# INC-IO1616001.net
KiCad netlist of a schematic drawn in Altium Designer
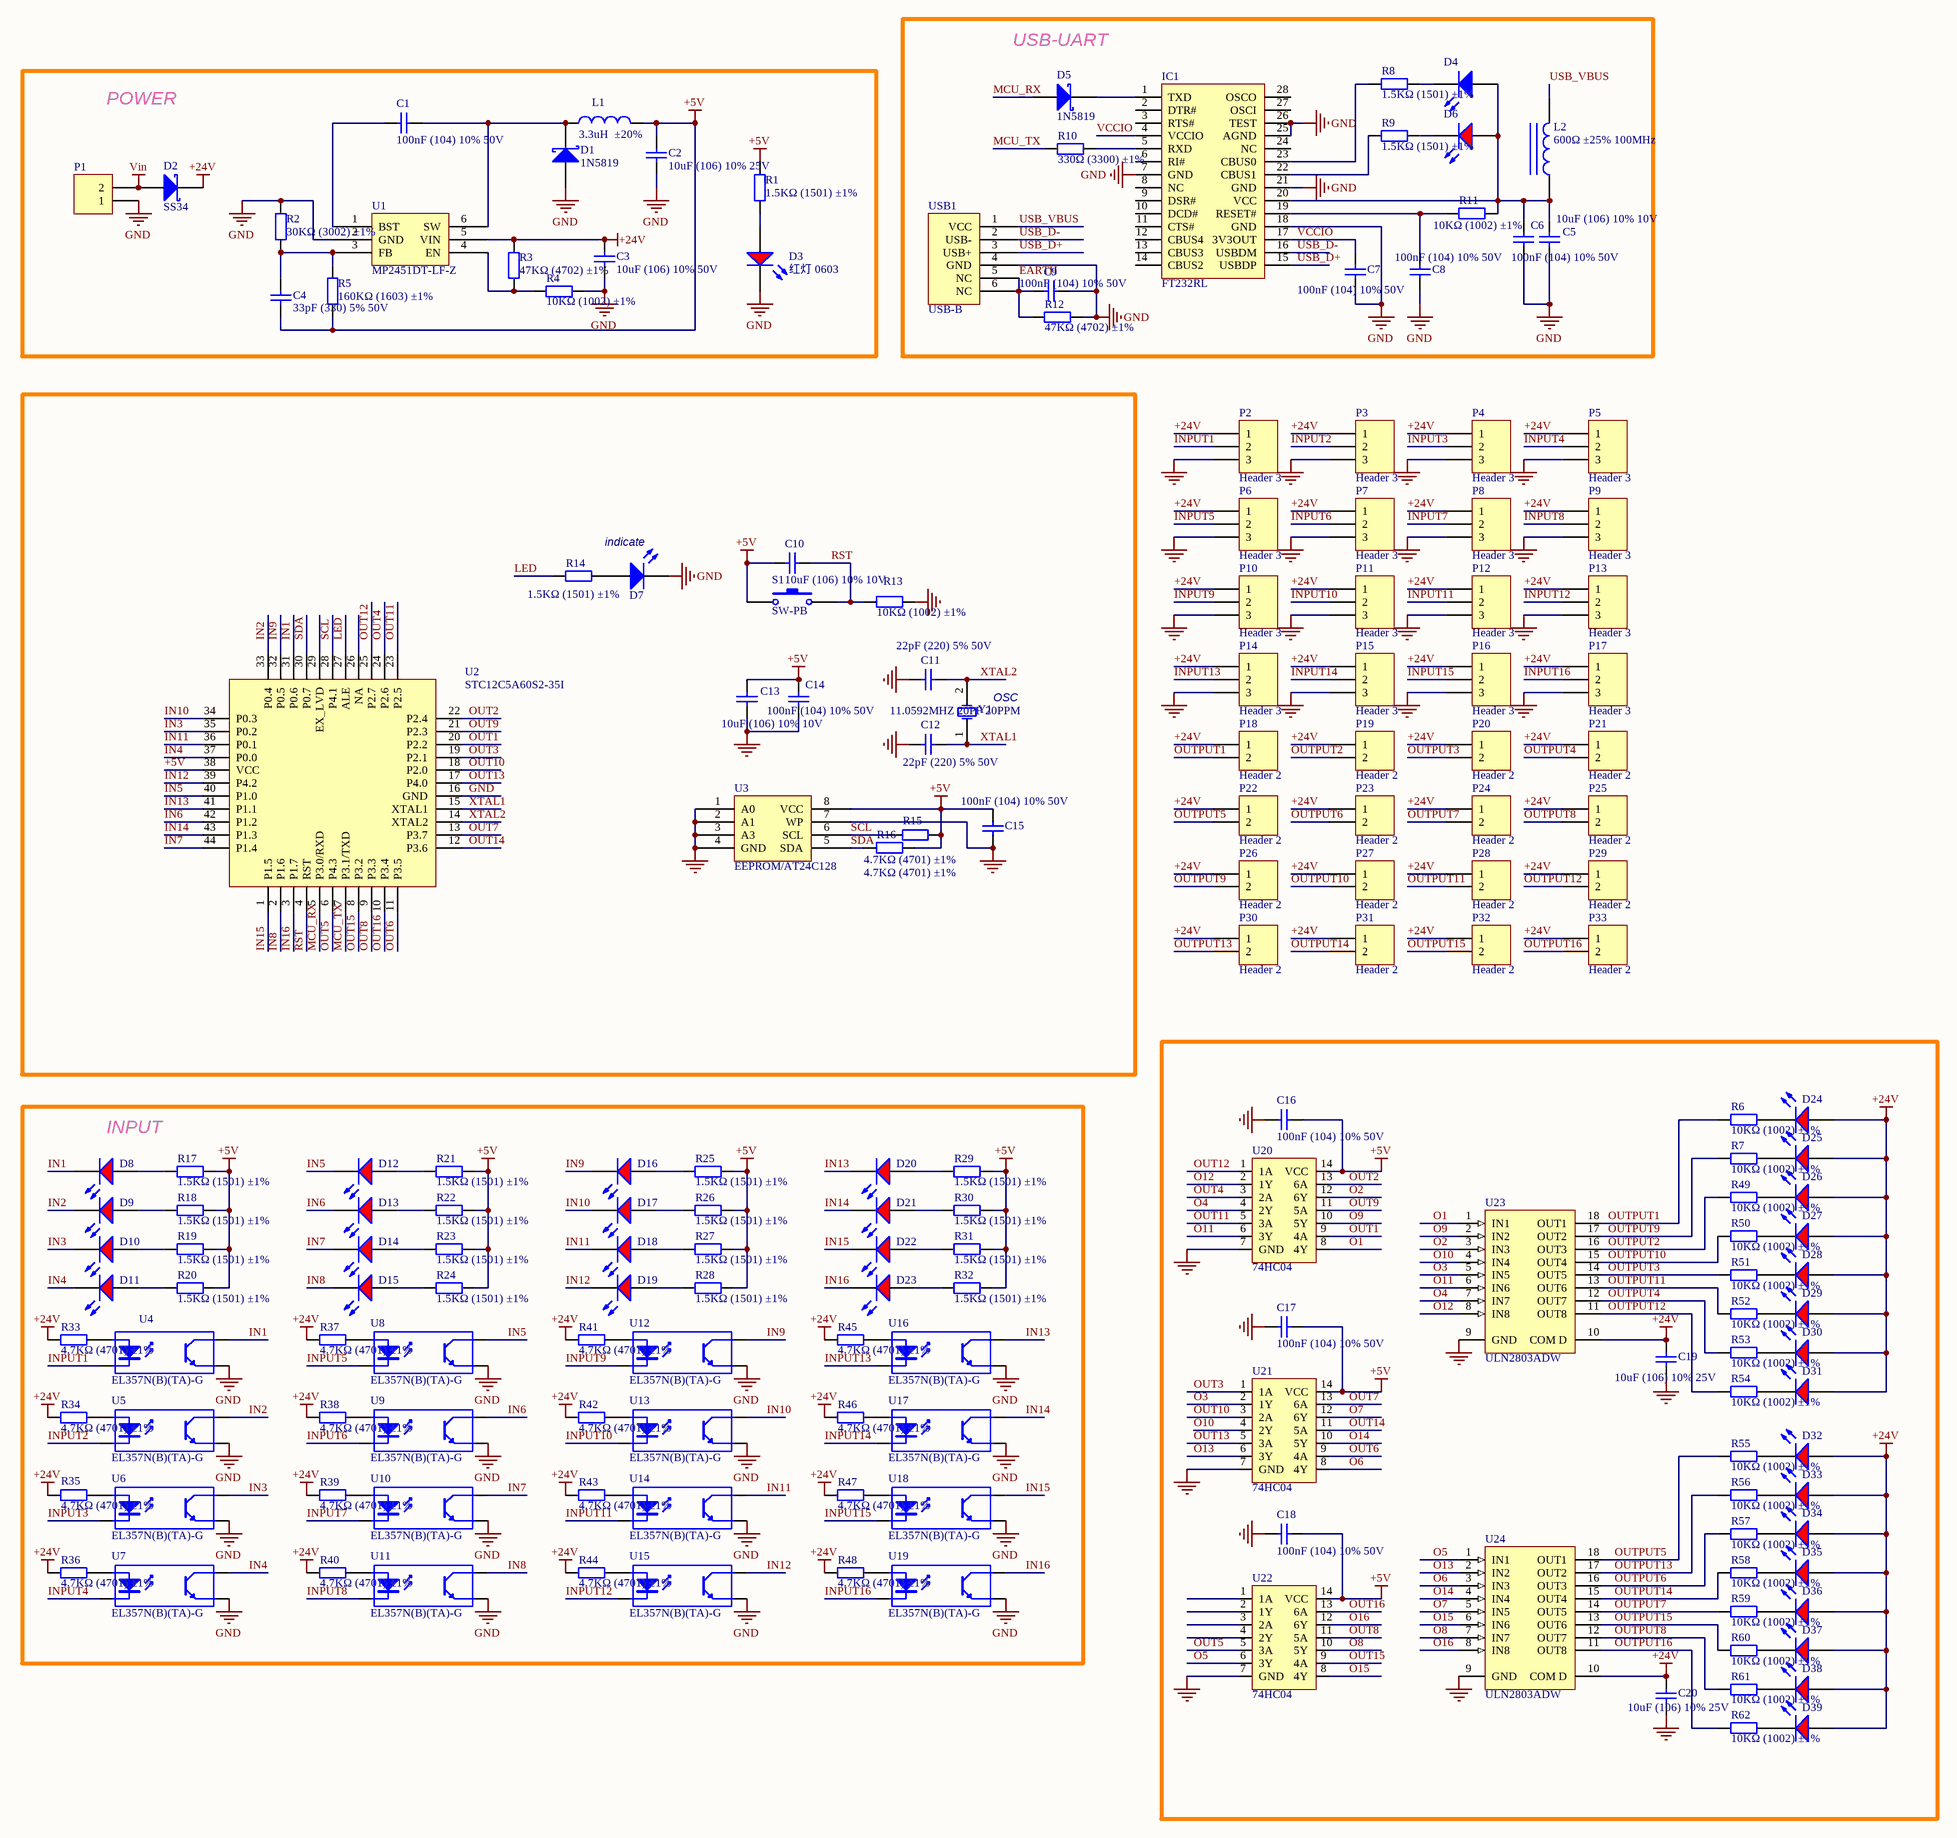
[diagram p0: INC-IO1616001.SchDoc]

(export (version "E")
  (design (tool "Eeschema 10.0.6"))
  (components
    (comp (ref "C1")
      (value "100nF (104) 10% 50V")
      (footprint "0603_C")
      (description "贴片电容")
      (libsource (lib "Miscellaneous Devices LC") (part "0603 100nF (104) 10% 50V"))
    )
    (comp (ref "C2")
      (value "10uF (106) 10% 25V")
      (footprint "0805_C")
      (description "贴片电容")
      (libsource (lib "Miscellaneous Devices LC") (part "0805 10uF (106) 10% 25V"))
    )
    (comp (ref "C3")
      (value "10uF (106) 10% 50V")
      (footprint "1206_C")
      (description "贴片电容")
      (libsource (lib "Miscellaneous Devices LC") (part "1206 10uF (106) 10% 50V"))
    )
    (comp (ref "C4")
      (value "33pF (330) 5% 50V")
      (footprint "0603_C")
      (description "贴片电容")
      (libsource (lib "Miscellaneous Devices LC") (part "0603 33pF (330) 5% 50V"))
    )
    (comp (ref "C5")
      (value "10uF (106) 10% 10V")
      (footprint "0603_C")
      (description "贴片电容")
      (libsource (lib "Miscellaneous Devices LC") (part "0603 10uF (106) 10% 10V"))
    )
    (comp (ref "C6")
      (value "100nF (104) 10% 50V")
      (footprint "0603_C")
      (description "贴片电容")
      (libsource (lib "Miscellaneous Devices LC") (part "0603 100nF (104) 10% 50V"))
    )
    (comp (ref "C7")
      (value "100nF (104) 10% 50V")
      (footprint "0603_C")
      (description "贴片电容")
      (libsource (lib "Miscellaneous Devices LC") (part "0603 100nF (104) 10% 50V"))
    )
    (comp (ref "C8")
      (value "100nF (104) 10% 50V")
      (footprint "0603_C")
      (description "贴片电容")
      (libsource (lib "Miscellaneous Devices LC") (part "0603 100nF (104) 10% 50V"))
    )
    (comp (ref "C9")
      (value "100nF (104) 10% 50V")
      (footprint "0603_C")
      (description "贴片电容")
      (libsource (lib "Miscellaneous Devices LC") (part "0603 100nF (104) 10% 50V"))
    )
    (comp (ref "C10")
      (value "10uF (106) 10% 10V")
      (footprint "0603_C")
      (description "贴片电容")
      (libsource (lib "Miscellaneous Devices LC") (part "0603 10uF (106) 10% 10V"))
    )
    (comp (ref "C11")
      (value "22pF (220) 5% 50V")
      (footprint "0603_C")
      (description "贴片电容")
      (libsource (lib "Miscellaneous Devices LC") (part "0603 22pF (220) 5% 50V"))
    )
    (comp (ref "C12")
      (value "22pF (220) 5% 50V")
      (footprint "0603_C")
      (description "贴片电容")
      (libsource (lib "Miscellaneous Devices LC") (part "0603 22pF (220) 5% 50V"))
    )
    (comp (ref "C13")
      (value "10uF (106) 10% 10V")
      (footprint "0603_C")
      (description "贴片电容")
      (libsource (lib "Miscellaneous Devices LC") (part "0603 10uF (106) 10% 10V"))
    )
    (comp (ref "C14")
      (value "100nF (104) 10% 50V")
      (footprint "0603_C")
      (description "贴片电容")
      (libsource (lib "Miscellaneous Devices LC") (part "0603 100nF (104) 10% 50V"))
    )
    (comp (ref "C15")
      (value "100nF (104) 10% 50V")
      (footprint "0603_C")
      (description "贴片电容")
      (libsource (lib "Miscellaneous Devices LC") (part "0603 100nF (104) 10% 50V"))
    )
    (comp (ref "C16")
      (value "100nF (104) 10% 50V")
      (footprint "0603_C")
      (description "贴片电容")
      (libsource (lib "Miscellaneous Devices LC") (part "0603 100nF (104) 10% 50V"))
    )
    (comp (ref "C17")
      (value "100nF (104) 10% 50V")
      (footprint "0603_C")
      (description "贴片电容")
      (libsource (lib "Miscellaneous Devices LC") (part "0603 100nF (104) 10% 50V"))
    )
    (comp (ref "C18")
      (value "100nF (104) 10% 50V")
      (footprint "0603_C")
      (description "贴片电容")
      (libsource (lib "Miscellaneous Devices LC") (part "0603 100nF (104) 10% 50V"))
    )
    (comp (ref "C19")
      (value "10uF (106) 10% 25V")
      (footprint "0805_C")
      (description "贴片电容")
      (libsource (lib "Miscellaneous Devices LC") (part "0805 10uF (106) 10% 25V"))
    )
    (comp (ref "C20")
      (value "10uF (106) 10% 25V")
      (footprint "0805_C")
      (description "贴片电容")
      (libsource (lib "Miscellaneous Devices LC") (part "0805 10uF (106) 10% 25V"))
    )
    (comp (ref "D1")
      (value "1N5819")
      (footprint "SOD-123")
      (description "Schottky Diode")
      (fields (field (name "PUBLISHER") "Altium Limited"))
      (libsource (lib "Miscellaneous Devices") (part "D Schottky"))
    )
    (comp (ref "D2")
      (value "SS34")
      (footprint "SMA(DO-214AC)_S1")
      (description "Schottky Diode")
      (fields (field (name "PUBLISHER") "Altium Limited"))
      (libsource (lib "Miscellaneous Devices") (part "D Schottky"))
    )
    (comp (ref "D3")
      (value "红灯 0603")
      (footprint "0603_LED_S1")
      (description "发光二极管")
      (libsource (lib "Miscellaneous Devices LC") (part "0603 红灯"))
    )
    (comp (ref "D4")
      (value "蓝灯 0603")
      (footprint "0603_LED_S1")
      (description "发光二极管")
      (libsource (lib "Miscellaneous Devices LC") (part "0603 蓝灯"))
    )
    (comp (ref "D5")
      (value "1N5819")
      (footprint "SOD-123")
      (description "Schottky Diode")
      (fields (field (name "PUBLISHER") "Altium Limited"))
      (libsource (lib "Miscellaneous Devices") (part "D Schottky"))
    )
    (comp (ref "D6")
      (value "红灯 0603")
      (footprint "0603_LED_S1")
      (description "发光二极管")
      (libsource (lib "Miscellaneous Devices LC") (part "0603 红灯"))
    )
    (comp (ref "D7")
      (value "蓝灯 0603")
      (footprint "0603_LED_S1")
      (description "发光二极管")
      (libsource (lib "Miscellaneous Devices LC") (part "0603 蓝灯"))
    )
    (comp (ref "D8")
      (value "红灯 0603")
      (footprint "0603_LED_S1")
      (description "发光二极管")
      (libsource (lib "Miscellaneous Devices LC") (part "0603 红灯"))
    )
    (comp (ref "D9")
      (value "红灯 0603")
      (footprint "0603_LED_S1")
      (description "发光二极管")
      (libsource (lib "Miscellaneous Devices LC") (part "0603 红灯"))
    )
    (comp (ref "D10")
      (value "红灯 0603")
      (footprint "0603_LED_S1")
      (description "发光二极管")
      (libsource (lib "Miscellaneous Devices LC") (part "0603 红灯"))
    )
    (comp (ref "D11")
      (value "红灯 0603")
      (footprint "0603_LED_S1")
      (description "发光二极管")
      (libsource (lib "Miscellaneous Devices LC") (part "0603 红灯"))
    )
    (comp (ref "D12")
      (value "红灯 0603")
      (footprint "0603_LED_S1")
      (description "发光二极管")
      (libsource (lib "Miscellaneous Devices LC") (part "0603 红灯"))
    )
    (comp (ref "D13")
      (value "红灯 0603")
      (footprint "0603_LED_S1")
      (description "发光二极管")
      (libsource (lib "Miscellaneous Devices LC") (part "0603 红灯"))
    )
    (comp (ref "D14")
      (value "红灯 0603")
      (footprint "0603_LED_S1")
      (description "发光二极管")
      (libsource (lib "Miscellaneous Devices LC") (part "0603 红灯"))
    )
    (comp (ref "D15")
      (value "红灯 0603")
      (footprint "0603_LED_S1")
      (description "发光二极管")
      (libsource (lib "Miscellaneous Devices LC") (part "0603 红灯"))
    )
    (comp (ref "D16")
      (value "红灯 0603")
      (footprint "0603_LED_S1")
      (description "发光二极管")
      (libsource (lib "Miscellaneous Devices LC") (part "0603 红灯"))
    )
    (comp (ref "D17")
      (value "红灯 0603")
      (footprint "0603_LED_S1")
      (description "发光二极管")
      (libsource (lib "Miscellaneous Devices LC") (part "0603 红灯"))
    )
    (comp (ref "D18")
      (value "红灯 0603")
      (footprint "0603_LED_S1")
      (description "发光二极管")
      (libsource (lib "Miscellaneous Devices LC") (part "0603 红灯"))
    )
    (comp (ref "D19")
      (value "红灯 0603")
      (footprint "0603_LED_S1")
      (description "发光二极管")
      (libsource (lib "Miscellaneous Devices LC") (part "0603 红灯"))
    )
    (comp (ref "D20")
      (value "红灯 0603")
      (footprint "0603_LED_S1")
      (description "发光二极管")
      (libsource (lib "Miscellaneous Devices LC") (part "0603 红灯"))
    )
    (comp (ref "D21")
      (value "红灯 0603")
      (footprint "0603_LED_S1")
      (description "发光二极管")
      (libsource (lib "Miscellaneous Devices LC") (part "0603 红灯"))
    )
    (comp (ref "D22")
      (value "红灯 0603")
      (footprint "0603_LED_S1")
      (description "发光二极管")
      (libsource (lib "Miscellaneous Devices LC") (part "0603 红灯"))
    )
    (comp (ref "D23")
      (value "红灯 0603")
      (footprint "0603_LED_S1")
      (description "发光二极管")
      (libsource (lib "Miscellaneous Devices LC") (part "0603 红灯"))
    )
    (comp (ref "D24")
      (value "红灯 0603")
      (footprint "0603_LED_S1")
      (description "发光二极管")
      (libsource (lib "Miscellaneous Devices LC") (part "0603 红灯"))
    )
    (comp (ref "D25")
      (value "红灯 0603")
      (footprint "0603_LED_S1")
      (description "发光二极管")
      (libsource (lib "Miscellaneous Devices LC") (part "0603 红灯"))
    )
    (comp (ref "D26")
      (value "红灯 0603")
      (footprint "0603_LED_S1")
      (description "发光二极管")
      (libsource (lib "Miscellaneous Devices LC") (part "0603 红灯"))
    )
    (comp (ref "D27")
      (value "红灯 0603")
      (footprint "0603_LED_S1")
      (description "发光二极管")
      (libsource (lib "Miscellaneous Devices LC") (part "0603 红灯"))
    )
    (comp (ref "D28")
      (value "红灯 0603")
      (footprint "0603_LED_S1")
      (description "发光二极管")
      (libsource (lib "Miscellaneous Devices LC") (part "0603 红灯"))
    )
    (comp (ref "D29")
      (value "红灯 0603")
      (footprint "0603_LED_S1")
      (description "发光二极管")
      (libsource (lib "Miscellaneous Devices LC") (part "0603 红灯"))
    )
    (comp (ref "D30")
      (value "红灯 0603")
      (footprint "0603_LED_S1")
      (description "发光二极管")
      (libsource (lib "Miscellaneous Devices LC") (part "0603 红灯"))
    )
    (comp (ref "D31")
      (value "红灯 0603")
      (footprint "0603_LED_S1")
      (description "发光二极管")
      (libsource (lib "Miscellaneous Devices LC") (part "0603 红灯"))
    )
    (comp (ref "D32")
      (value "红灯 0603")
      (footprint "0603_LED_S1")
      (description "发光二极管")
      (libsource (lib "Miscellaneous Devices LC") (part "0603 红灯"))
    )
    (comp (ref "D33")
      (value "红灯 0603")
      (footprint "0603_LED_S1")
      (description "发光二极管")
      (libsource (lib "Miscellaneous Devices LC") (part "0603 红灯"))
    )
    (comp (ref "D34")
      (value "红灯 0603")
      (footprint "0603_LED_S1")
      (description "发光二极管")
      (libsource (lib "Miscellaneous Devices LC") (part "0603 红灯"))
    )
    (comp (ref "D35")
      (value "红灯 0603")
      (footprint "0603_LED_S1")
      (description "发光二极管")
      (libsource (lib "Miscellaneous Devices LC") (part "0603 红灯"))
    )
    (comp (ref "D36")
      (value "红灯 0603")
      (footprint "0603_LED_S1")
      (description "发光二极管")
      (libsource (lib "Miscellaneous Devices LC") (part "0603 红灯"))
    )
    (comp (ref "D37")
      (value "红灯 0603")
      (footprint "0603_LED_S1")
      (description "发光二极管")
      (libsource (lib "Miscellaneous Devices LC") (part "0603 红灯"))
    )
    (comp (ref "D38")
      (value "红灯 0603")
      (footprint "0603_LED_S1")
      (description "发光二极管")
      (libsource (lib "Miscellaneous Devices LC") (part "0603 红灯"))
    )
    (comp (ref "D39")
      (value "红灯 0603")
      (footprint "0603_LED_S1")
      (description "发光二极管")
      (libsource (lib "Miscellaneous Devices LC") (part "0603 红灯"))
    )
    (comp (ref "IC1")
      (value "FT232RL")
      (footprint "SSOP-28_208mil")
      (libsource (lib "GB-SCH") (part "FT232RL"))
    )
    (comp (ref "L1")
      (value "3.3uH  ±20%")
      (footprint "L5020")
      (description "Inductor")
      (fields (field (name "PUBLISHER") "Altium Limited"))
      (libsource (lib "Miscellaneous Devices") (part "Inductor"))
    )
    (comp (ref "L2")
      (value "600Ω ±25% 100MHz")
      (footprint "0805_L")
      (description "贴片磁珠")
      (libsource (lib "Miscellaneous Devices LC") (part "0805 600Ω 25% 100MHz"))
    )
    (comp (ref "P1")
      (value "Header 2")
      (footprint "WJ15EDGVC-3.81-2P")
      (description "Header, 2-Pin")
      (fields (field (name "PUBLISHER") "Altium Limited"))
      (libsource (lib "") (part "Header 2_1"))
    )
    (comp (ref "P2")
      (value "Header 3")
      (footprint "WJ15EDGVC-3.81-3P")
      (description "Header, 3-Pin")
      (fields (field (name "PUBLISHER") "Altium Limited"))
      (libsource (lib "Miscellaneous Connectors") (part "Header 3"))
    )
    (comp (ref "P3")
      (value "Header 3")
      (footprint "WJ15EDGVC-3.81-3P")
      (description "Header, 3-Pin")
      (fields (field (name "PUBLISHER") "Altium Limited"))
      (libsource (lib "Miscellaneous Connectors") (part "Header 3"))
    )
    (comp (ref "P4")
      (value "Header 3")
      (footprint "WJ15EDGVC-3.81-3P")
      (description "Header, 3-Pin")
      (fields (field (name "PUBLISHER") "Altium Limited"))
      (libsource (lib "Miscellaneous Connectors") (part "Header 3"))
    )
    (comp (ref "P5")
      (value "Header 3")
      (footprint "WJ15EDGVC-3.81-3P")
      (description "Header, 3-Pin")
      (fields (field (name "PUBLISHER") "Altium Limited"))
      (libsource (lib "Miscellaneous Connectors") (part "Header 3"))
    )
    (comp (ref "P6")
      (value "Header 3")
      (footprint "WJ15EDGVC-3.81-3P")
      (description "Header, 3-Pin")
      (fields (field (name "PUBLISHER") "Altium Limited"))
      (libsource (lib "Miscellaneous Connectors") (part "Header 3"))
    )
    (comp (ref "P7")
      (value "Header 3")
      (footprint "WJ15EDGVC-3.81-3P")
      (description "Header, 3-Pin")
      (fields (field (name "PUBLISHER") "Altium Limited"))
      (libsource (lib "Miscellaneous Connectors") (part "Header 3"))
    )
    (comp (ref "P8")
      (value "Header 3")
      (footprint "WJ15EDGVC-3.81-3P")
      (description "Header, 3-Pin")
      (fields (field (name "PUBLISHER") "Altium Limited"))
      (libsource (lib "Miscellaneous Connectors") (part "Header 3"))
    )
    (comp (ref "P9")
      (value "Header 3")
      (footprint "WJ15EDGVC-3.81-3P")
      (description "Header, 3-Pin")
      (fields (field (name "PUBLISHER") "Altium Limited"))
      (libsource (lib "Miscellaneous Connectors") (part "Header 3"))
    )
    (comp (ref "P10")
      (value "Header 3")
      (footprint "WJ15EDGVC-3.81-3P")
      (description "Header, 3-Pin")
      (fields (field (name "PUBLISHER") "Altium Limited"))
      (libsource (lib "Miscellaneous Connectors") (part "Header 3"))
    )
    (comp (ref "P11")
      (value "Header 3")
      (footprint "WJ15EDGVC-3.81-3P")
      (description "Header, 3-Pin")
      (fields (field (name "PUBLISHER") "Altium Limited"))
      (libsource (lib "Miscellaneous Connectors") (part "Header 3"))
    )
    (comp (ref "P12")
      (value "Header 3")
      (footprint "WJ15EDGVC-3.81-3P")
      (description "Header, 3-Pin")
      (fields (field (name "PUBLISHER") "Altium Limited"))
      (libsource (lib "Miscellaneous Connectors") (part "Header 3"))
    )
    (comp (ref "P13")
      (value "Header 3")
      (footprint "WJ15EDGVC-3.81-3P")
      (description "Header, 3-Pin")
      (fields (field (name "PUBLISHER") "Altium Limited"))
      (libsource (lib "Miscellaneous Connectors") (part "Header 3"))
    )
    (comp (ref "P14")
      (value "Header 3")
      (footprint "WJ15EDGVC-3.81-3P")
      (description "Header, 3-Pin")
      (fields (field (name "PUBLISHER") "Altium Limited"))
      (libsource (lib "Miscellaneous Connectors") (part "Header 3"))
    )
    (comp (ref "P15")
      (value "Header 3")
      (footprint "WJ15EDGVC-3.81-3P")
      (description "Header, 3-Pin")
      (fields (field (name "PUBLISHER") "Altium Limited"))
      (libsource (lib "Miscellaneous Connectors") (part "Header 3"))
    )
    (comp (ref "P16")
      (value "Header 3")
      (footprint "WJ15EDGVC-3.81-3P")
      (description "Header, 3-Pin")
      (fields (field (name "PUBLISHER") "Altium Limited"))
      (libsource (lib "Miscellaneous Connectors") (part "Header 3"))
    )
    (comp (ref "P17")
      (value "Header 3")
      (footprint "WJ15EDGVC-3.81-3P")
      (description "Header, 3-Pin")
      (fields (field (name "PUBLISHER") "Altium Limited"))
      (libsource (lib "Miscellaneous Connectors") (part "Header 3"))
    )
    (comp (ref "P18")
      (value "Header 2")
      (footprint "WJ15EDGVC-3.81-2P")
      (description "Header, 2-Pin")
      (fields (field (name "PUBLISHER") "Altium Limited"))
      (libsource (lib "Miscellaneous Connectors") (part "Header 2"))
    )
    (comp (ref "P19")
      (value "Header 2")
      (footprint "WJ15EDGVC-3.81-2P")
      (description "Header, 2-Pin")
      (fields (field (name "PUBLISHER") "Altium Limited"))
      (libsource (lib "Miscellaneous Connectors") (part "Header 2"))
    )
    (comp (ref "P20")
      (value "Header 2")
      (footprint "WJ15EDGVC-3.81-2P")
      (description "Header, 2-Pin")
      (fields (field (name "PUBLISHER") "Altium Limited"))
      (libsource (lib "Miscellaneous Connectors") (part "Header 2"))
    )
    (comp (ref "P21")
      (value "Header 2")
      (footprint "WJ15EDGVC-3.81-2P")
      (description "Header, 2-Pin")
      (fields (field (name "PUBLISHER") "Altium Limited"))
      (libsource (lib "Miscellaneous Connectors") (part "Header 2"))
    )
    (comp (ref "P22")
      (value "Header 2")
      (footprint "WJ15EDGVC-3.81-2P")
      (description "Header, 2-Pin")
      (fields (field (name "PUBLISHER") "Altium Limited"))
      (libsource (lib "Miscellaneous Connectors") (part "Header 2"))
    )
    (comp (ref "P23")
      (value "Header 2")
      (footprint "WJ15EDGVC-3.81-2P")
      (description "Header, 2-Pin")
      (fields (field (name "PUBLISHER") "Altium Limited"))
      (libsource (lib "Miscellaneous Connectors") (part "Header 2"))
    )
    (comp (ref "P24")
      (value "Header 2")
      (footprint "WJ15EDGVC-3.81-2P")
      (description "Header, 2-Pin")
      (fields (field (name "PUBLISHER") "Altium Limited"))
      (libsource (lib "Miscellaneous Connectors") (part "Header 2"))
    )
    (comp (ref "P25")
      (value "Header 2")
      (footprint "WJ15EDGVC-3.81-2P")
      (description "Header, 2-Pin")
      (fields (field (name "PUBLISHER") "Altium Limited"))
      (libsource (lib "Miscellaneous Connectors") (part "Header 2"))
    )
    (comp (ref "P26")
      (value "Header 2")
      (footprint "WJ15EDGVC-3.81-2P")
      (description "Header, 2-Pin")
      (fields (field (name "PUBLISHER") "Altium Limited"))
      (libsource (lib "Miscellaneous Connectors") (part "Header 2"))
    )
    (comp (ref "P27")
      (value "Header 2")
      (footprint "WJ15EDGVC-3.81-2P")
      (description "Header, 2-Pin")
      (fields (field (name "PUBLISHER") "Altium Limited"))
      (libsource (lib "Miscellaneous Connectors") (part "Header 2"))
    )
    (comp (ref "P28")
      (value "Header 2")
      (footprint "WJ15EDGVC-3.81-2P")
      (description "Header, 2-Pin")
      (fields (field (name "PUBLISHER") "Altium Limited"))
      (libsource (lib "Miscellaneous Connectors") (part "Header 2"))
    )
    (comp (ref "P29")
      (value "Header 2")
      (footprint "WJ15EDGVC-3.81-2P")
      (description "Header, 2-Pin")
      (fields (field (name "PUBLISHER") "Altium Limited"))
      (libsource (lib "Miscellaneous Connectors") (part "Header 2"))
    )
    (comp (ref "P30")
      (value "Header 2")
      (footprint "WJ15EDGVC-3.81-2P")
      (description "Header, 2-Pin")
      (fields (field (name "PUBLISHER") "Altium Limited"))
      (libsource (lib "Miscellaneous Connectors") (part "Header 2"))
    )
    (comp (ref "P31")
      (value "Header 2")
      (footprint "WJ15EDGVC-3.81-2P")
      (description "Header, 2-Pin")
      (fields (field (name "PUBLISHER") "Altium Limited"))
      (libsource (lib "Miscellaneous Connectors") (part "Header 2"))
    )
    (comp (ref "P32")
      (value "Header 2")
      (footprint "WJ15EDGVC-3.81-2P")
      (description "Header, 2-Pin")
      (fields (field (name "PUBLISHER") "Altium Limited"))
      (libsource (lib "Miscellaneous Connectors") (part "Header 2"))
    )
    (comp (ref "P33")
      (value "Header 2")
      (footprint "WJ15EDGVC-3.81-2P")
      (description "Header, 2-Pin")
      (fields (field (name "PUBLISHER") "Altium Limited"))
      (libsource (lib "Miscellaneous Connectors") (part "Header 2"))
    )
    (comp (ref "R1")
      (value "1.5KΩ (1501) ±1%")
      (footprint "0603_R")
      (description "贴片电阻")
      (libsource (lib "") (part "0603 1.5KΩ (1501) 1%_2"))
    )
    (comp (ref "R2")
      (value "30KΩ (3002) ±1%")
      (footprint "0603_R")
      (description "贴片电阻")
      (libsource (lib "Miscellaneous Devices LC") (part "0603 30KΩ (3002) 1%"))
    )
    (comp (ref "R3")
      (value "47KΩ (4702) ±1%")
      (footprint "0603_R")
      (description "贴片电阻")
      (libsource (lib "") (part "0603 47KΩ (4702) 1%_1"))
    )
    (comp (ref "R4")
      (value "10KΩ (1002) ±1%")
      (footprint "0603_R")
      (description "贴片电阻")
      (libsource (lib "Miscellaneous Devices LC") (part "0603 10KΩ (1002) 1%"))
    )
    (comp (ref "R5")
      (value "160KΩ (1603) ±1%")
      (footprint "0603_R")
      (description "贴片电阻")
      (libsource (lib "Miscellaneous Devices LC") (part "0603 160KΩ (1603) 1%"))
    )
    (comp (ref "R6")
      (value "10KΩ (1002) ±1%")
      (footprint "0603_R")
      (description "贴片电阻")
      (libsource (lib "Miscellaneous Devices LC") (part "0603 10KΩ (1002) 1%"))
    )
    (comp (ref "R7")
      (value "10KΩ (1002) ±1%")
      (footprint "0603_R")
      (description "贴片电阻")
      (libsource (lib "Miscellaneous Devices LC") (part "0603 10KΩ (1002) 1%"))
    )
    (comp (ref "R8")
      (value "1.5KΩ (1501) ±1%")
      (footprint "0603_R")
      (description "贴片电阻")
      (libsource (lib "") (part "0603 1.5KΩ (1501) 1%_1"))
    )
    (comp (ref "R9")
      (value "1.5KΩ (1501) ±1%")
      (footprint "0603_R")
      (description "贴片电阻")
      (libsource (lib "") (part "0603 1.5KΩ (1501) 1%_1"))
    )
    (comp (ref "R10")
      (value "330Ω (3300) ±1%")
      (footprint "0603_R")
      (description "贴片电阻")
      (libsource (lib "Miscellaneous Devices LC") (part "0603 330Ω (3300) 1%"))
    )
    (comp (ref "R11")
      (value "10KΩ (1002) ±1%")
      (footprint "0603_R")
      (description "贴片电阻")
      (libsource (lib "Miscellaneous Devices LC") (part "0603 10KΩ (1002) 1%"))
    )
    (comp (ref "R12")
      (value "47KΩ (4702) ±1%")
      (footprint "0603_R")
      (description "贴片电阻")
      (libsource (lib "Miscellaneous Devices LC") (part "0603 47KΩ (4702) 1%"))
    )
    (comp (ref "R13")
      (value "10KΩ (1002) ±1%")
      (footprint "0603_R")
      (description "贴片电阻")
      (libsource (lib "Miscellaneous Devices LC") (part "0603 10KΩ (1002) 1%"))
    )
    (comp (ref "R14")
      (value "1.5KΩ (1501) ±1%")
      (footprint "0603_R")
      (description "贴片电阻")
      (libsource (lib "Miscellaneous Devices LC") (part "0603 1.5KΩ (1501) 1%"))
    )
    (comp (ref "R15")
      (value "4.7KΩ (4701) ±1%")
      (footprint "0603_R")
      (description "贴片电阻")
      (libsource (lib "Miscellaneous Devices LC") (part "0603 4.7KΩ (4701) 1%"))
    )
    (comp (ref "R16")
      (value "4.7KΩ (4701) ±1%")
      (footprint "0603_R")
      (description "贴片电阻")
      (libsource (lib "Miscellaneous Devices LC") (part "0603 4.7KΩ (4701) 1%"))
    )
    (comp (ref "R17")
      (value "1.5KΩ (1501) ±1%")
      (footprint "0603_R")
      (description "贴片电阻")
      (libsource (lib "Miscellaneous Devices LC") (part "0603 1.5KΩ (1501) 1%"))
    )
    (comp (ref "R18")
      (value "1.5KΩ (1501) ±1%")
      (footprint "0603_R")
      (description "贴片电阻")
      (libsource (lib "Miscellaneous Devices LC") (part "0603 1.5KΩ (1501) 1%"))
    )
    (comp (ref "R19")
      (value "1.5KΩ (1501) ±1%")
      (footprint "0603_R")
      (description "贴片电阻")
      (libsource (lib "Miscellaneous Devices LC") (part "0603 1.5KΩ (1501) 1%"))
    )
    (comp (ref "R20")
      (value "1.5KΩ (1501) ±1%")
      (footprint "0603_R")
      (description "贴片电阻")
      (libsource (lib "Miscellaneous Devices LC") (part "0603 1.5KΩ (1501) 1%"))
    )
    (comp (ref "R21")
      (value "1.5KΩ (1501) ±1%")
      (footprint "0603_R")
      (description "贴片电阻")
      (libsource (lib "Miscellaneous Devices LC") (part "0603 1.5KΩ (1501) 1%"))
    )
    (comp (ref "R22")
      (value "1.5KΩ (1501) ±1%")
      (footprint "0603_R")
      (description "贴片电阻")
      (libsource (lib "Miscellaneous Devices LC") (part "0603 1.5KΩ (1501) 1%"))
    )
    (comp (ref "R23")
      (value "1.5KΩ (1501) ±1%")
      (footprint "0603_R")
      (description "贴片电阻")
      (libsource (lib "Miscellaneous Devices LC") (part "0603 1.5KΩ (1501) 1%"))
    )
    (comp (ref "R24")
      (value "1.5KΩ (1501) ±1%")
      (footprint "0603_R")
      (description "贴片电阻")
      (libsource (lib "Miscellaneous Devices LC") (part "0603 1.5KΩ (1501) 1%"))
    )
    (comp (ref "R25")
      (value "1.5KΩ (1501) ±1%")
      (footprint "0603_R")
      (description "贴片电阻")
      (libsource (lib "Miscellaneous Devices LC") (part "0603 1.5KΩ (1501) 1%"))
    )
    (comp (ref "R26")
      (value "1.5KΩ (1501) ±1%")
      (footprint "0603_R")
      (description "贴片电阻")
      (libsource (lib "Miscellaneous Devices LC") (part "0603 1.5KΩ (1501) 1%"))
    )
    (comp (ref "R27")
      (value "1.5KΩ (1501) ±1%")
      (footprint "0603_R")
      (description "贴片电阻")
      (libsource (lib "Miscellaneous Devices LC") (part "0603 1.5KΩ (1501) 1%"))
    )
    (comp (ref "R28")
      (value "1.5KΩ (1501) ±1%")
      (footprint "0603_R")
      (description "贴片电阻")
      (libsource (lib "Miscellaneous Devices LC") (part "0603 1.5KΩ (1501) 1%"))
    )
    (comp (ref "R29")
      (value "1.5KΩ (1501) ±1%")
      (footprint "0603_R")
      (description "贴片电阻")
      (libsource (lib "Miscellaneous Devices LC") (part "0603 1.5KΩ (1501) 1%"))
    )
    (comp (ref "R30")
      (value "1.5KΩ (1501) ±1%")
      (footprint "0603_R")
      (description "贴片电阻")
      (libsource (lib "Miscellaneous Devices LC") (part "0603 1.5KΩ (1501) 1%"))
    )
    (comp (ref "R31")
      (value "1.5KΩ (1501) ±1%")
      (footprint "0603_R")
      (description "贴片电阻")
      (libsource (lib "Miscellaneous Devices LC") (part "0603 1.5KΩ (1501) 1%"))
    )
    (comp (ref "R32")
      (value "1.5KΩ (1501) ±1%")
      (footprint "0603_R")
      (description "贴片电阻")
      (libsource (lib "Miscellaneous Devices LC") (part "0603 1.5KΩ (1501) 1%"))
    )
    (comp (ref "R33")
      (value "4.7KΩ (4701) ±1%")
      (footprint "1206_R")
      (description "贴片电阻")
      (libsource (lib "Miscellaneous Devices LC") (part "1206 4.7KΩ (4701) 1%"))
    )
    (comp (ref "R34")
      (value "4.7KΩ (4701) ±1%")
      (footprint "1206_R")
      (description "贴片电阻")
      (libsource (lib "Miscellaneous Devices LC") (part "1206 4.7KΩ (4701) 1%"))
    )
    (comp (ref "R35")
      (value "4.7KΩ (4701) ±1%")
      (footprint "1206_R")
      (description "贴片电阻")
      (libsource (lib "Miscellaneous Devices LC") (part "1206 4.7KΩ (4701) 1%"))
    )
    (comp (ref "R36")
      (value "4.7KΩ (4701) ±1%")
      (footprint "1206_R")
      (description "贴片电阻")
      (libsource (lib "Miscellaneous Devices LC") (part "1206 4.7KΩ (4701) 1%"))
    )
    (comp (ref "R37")
      (value "4.7KΩ (4701) ±1%")
      (footprint "1206_R")
      (description "贴片电阻")
      (libsource (lib "Miscellaneous Devices LC") (part "1206 4.7KΩ (4701) 1%"))
    )
    (comp (ref "R38")
      (value "4.7KΩ (4701) ±1%")
      (footprint "1206_R")
      (description "贴片电阻")
      (libsource (lib "Miscellaneous Devices LC") (part "1206 4.7KΩ (4701) 1%"))
    )
    (comp (ref "R39")
      (value "4.7KΩ (4701) ±1%")
      (footprint "1206_R")
      (description "贴片电阻")
      (libsource (lib "Miscellaneous Devices LC") (part "1206 4.7KΩ (4701) 1%"))
    )
    (comp (ref "R40")
      (value "4.7KΩ (4701) ±1%")
      (footprint "1206_R")
      (description "贴片电阻")
      (libsource (lib "Miscellaneous Devices LC") (part "1206 4.7KΩ (4701) 1%"))
    )
    (comp (ref "R41")
      (value "4.7KΩ (4701) ±1%")
      (footprint "1206_R")
      (description "贴片电阻")
      (libsource (lib "Miscellaneous Devices LC") (part "1206 4.7KΩ (4701) 1%"))
    )
    (comp (ref "R42")
      (value "4.7KΩ (4701) ±1%")
      (footprint "1206_R")
      (description "贴片电阻")
      (libsource (lib "Miscellaneous Devices LC") (part "1206 4.7KΩ (4701) 1%"))
    )
    (comp (ref "R43")
      (value "4.7KΩ (4701) ±1%")
      (footprint "1206_R")
      (description "贴片电阻")
      (libsource (lib "Miscellaneous Devices LC") (part "1206 4.7KΩ (4701) 1%"))
    )
    (comp (ref "R44")
      (value "4.7KΩ (4701) ±1%")
      (footprint "1206_R")
      (description "贴片电阻")
      (libsource (lib "Miscellaneous Devices LC") (part "1206 4.7KΩ (4701) 1%"))
    )
    (comp (ref "R45")
      (value "4.7KΩ (4701) ±1%")
      (footprint "1206_R")
      (description "贴片电阻")
      (libsource (lib "Miscellaneous Devices LC") (part "1206 4.7KΩ (4701) 1%"))
    )
    (comp (ref "R46")
      (value "4.7KΩ (4701) ±1%")
      (footprint "1206_R")
      (description "贴片电阻")
      (libsource (lib "Miscellaneous Devices LC") (part "1206 4.7KΩ (4701) 1%"))
    )
    (comp (ref "R47")
      (value "4.7KΩ (4701) ±1%")
      (footprint "1206_R")
      (description "贴片电阻")
      (libsource (lib "Miscellaneous Devices LC") (part "1206 4.7KΩ (4701) 1%"))
    )
    (comp (ref "R48")
      (value "4.7KΩ (4701) ±1%")
      (footprint "1206_R")
      (description "贴片电阻")
      (libsource (lib "Miscellaneous Devices LC") (part "1206 4.7KΩ (4701) 1%"))
    )
    (comp (ref "R49")
      (value "10KΩ (1002) ±1%")
      (footprint "0603_R")
      (description "贴片电阻")
      (libsource (lib "Miscellaneous Devices LC") (part "0603 10KΩ (1002) 1%"))
    )
    (comp (ref "R50")
      (value "10KΩ (1002) ±1%")
      (footprint "0603_R")
      (description "贴片电阻")
      (libsource (lib "Miscellaneous Devices LC") (part "0603 10KΩ (1002) 1%"))
    )
    (comp (ref "R51")
      (value "10KΩ (1002) ±1%")
      (footprint "0603_R")
      (description "贴片电阻")
      (libsource (lib "Miscellaneous Devices LC") (part "0603 10KΩ (1002) 1%"))
    )
    (comp (ref "R52")
      (value "10KΩ (1002) ±1%")
      (footprint "0603_R")
      (description "贴片电阻")
      (libsource (lib "Miscellaneous Devices LC") (part "0603 10KΩ (1002) 1%"))
    )
    (comp (ref "R53")
      (value "10KΩ (1002) ±1%")
      (footprint "0603_R")
      (description "贴片电阻")
      (libsource (lib "Miscellaneous Devices LC") (part "0603 10KΩ (1002) 1%"))
    )
    (comp (ref "R54")
      (value "10KΩ (1002) ±1%")
      (footprint "0603_R")
      (description "贴片电阻")
      (libsource (lib "Miscellaneous Devices LC") (part "0603 10KΩ (1002) 1%"))
    )
    (comp (ref "R55")
      (value "10KΩ (1002) ±1%")
      (footprint "0603_R")
      (description "贴片电阻")
      (libsource (lib "Miscellaneous Devices LC") (part "0603 10KΩ (1002) 1%"))
    )
    (comp (ref "R56")
      (value "10KΩ (1002) ±1%")
      (footprint "0603_R")
      (description "贴片电阻")
      (libsource (lib "Miscellaneous Devices LC") (part "0603 10KΩ (1002) 1%"))
    )
    (comp (ref "R57")
      (value "10KΩ (1002) ±1%")
      (footprint "0603_R")
      (description "贴片电阻")
      (libsource (lib "Miscellaneous Devices LC") (part "0603 10KΩ (1002) 1%"))
    )
    (comp (ref "R58")
      (value "10KΩ (1002) ±1%")
      (footprint "0603_R")
      (description "贴片电阻")
      (libsource (lib "Miscellaneous Devices LC") (part "0603 10KΩ (1002) 1%"))
    )
    (comp (ref "R59")
      (value "10KΩ (1002) ±1%")
      (footprint "0603_R")
      (description "贴片电阻")
      (libsource (lib "Miscellaneous Devices LC") (part "0603 10KΩ (1002) 1%"))
    )
    (comp (ref "R60")
      (value "10KΩ (1002) ±1%")
      (footprint "0603_R")
      (description "贴片电阻")
      (libsource (lib "Miscellaneous Devices LC") (part "0603 10KΩ (1002) 1%"))
    )
    (comp (ref "R61")
      (value "10KΩ (1002) ±1%")
      (footprint "0603_R")
      (description "贴片电阻")
      (libsource (lib "Miscellaneous Devices LC") (part "0603 10KΩ (1002) 1%"))
    )
    (comp (ref "R62")
      (value "10KΩ (1002) ±1%")
      (footprint "0603_R")
      (description "贴片电阻")
      (libsource (lib "Miscellaneous Devices LC") (part "0603 10KΩ (1002) 1%"))
    )
    (comp (ref "S1")
      (value "SW-PB")
      (footprint "贴片按键 3*6*2.5")
      (description "Switch")
      (fields (field (name "PUBLISHER") "Altium Limited"))
      (libsource (lib "Miscellaneous Devices") (part "SW-PB"))
    )
    (comp (ref "U1")
      (value "MP2451DT-LF-Z")
      (footprint "SOT-23-6")
      (description "DC-DC芯片")
      (libsource (lib "Miscellaneous Devices LC") (part "MP2451DT-LF-Z"))
    )
    (comp (ref "U2")
      (value "STC12C5A60S2-35I")
      (footprint "LQFP-44_10x10x08P")
      (description "MCU")
      (libsource (lib "Miscellaneous Devices LC") (part "STC12C5A60S2-35I"))
    )
    (comp (ref "U3")
      (value "EEPROM/AT24C128")
      (footprint "SOIC-8_150mil")
      (description "EEPROM")
      (libsource (lib "Miscellaneous Devices LC") (part "EEPROM/AT24C256C-SSHL-T"))
    )
    (comp (ref "U4")
      (value "EL357N(B)(TA)-G")
      (footprint "SOP-4_P2.54")
      (description "贴片光耦")
      (libsource (lib "Miscellaneous Devices LC") (part "EL357N(B)(TA)-G"))
    )
    (comp (ref "U5")
      (value "EL357N(B)(TA)-G")
      (footprint "SOP-4_P2.54")
      (description "贴片光耦")
      (libsource (lib "Miscellaneous Devices LC") (part "EL357N(B)(TA)-G"))
    )
    (comp (ref "U6")
      (value "EL357N(B)(TA)-G")
      (footprint "SOP-4_P2.54")
      (description "贴片光耦")
      (libsource (lib "Miscellaneous Devices LC") (part "EL357N(B)(TA)-G"))
    )
    (comp (ref "U7")
      (value "EL357N(B)(TA)-G")
      (footprint "SOP-4_P2.54")
      (description "贴片光耦")
      (libsource (lib "Miscellaneous Devices LC") (part "EL357N(B)(TA)-G"))
    )
    (comp (ref "U8")
      (value "EL357N(B)(TA)-G")
      (footprint "SOP-4_P2.54")
      (description "贴片光耦")
      (libsource (lib "Miscellaneous Devices LC") (part "EL357N(B)(TA)-G"))
    )
    (comp (ref "U9")
      (value "EL357N(B)(TA)-G")
      (footprint "SOP-4_P2.54")
      (description "贴片光耦")
      (libsource (lib "Miscellaneous Devices LC") (part "EL357N(B)(TA)-G"))
    )
    (comp (ref "U10")
      (value "EL357N(B)(TA)-G")
      (footprint "SOP-4_P2.54")
      (description "贴片光耦")
      (libsource (lib "Miscellaneous Devices LC") (part "EL357N(B)(TA)-G"))
    )
    (comp (ref "U11")
      (value "EL357N(B)(TA)-G")
      (footprint "SOP-4_P2.54")
      (description "贴片光耦")
      (libsource (lib "Miscellaneous Devices LC") (part "EL357N(B)(TA)-G"))
    )
    (comp (ref "U12")
      (value "EL357N(B)(TA)-G")
      (footprint "SOP-4_P2.54")
      (description "贴片光耦")
      (libsource (lib "Miscellaneous Devices LC") (part "EL357N(B)(TA)-G"))
    )
    (comp (ref "U13")
      (value "EL357N(B)(TA)-G")
      (footprint "SOP-4_P2.54")
      (description "贴片光耦")
      (libsource (lib "Miscellaneous Devices LC") (part "EL357N(B)(TA)-G"))
    )
    (comp (ref "U14")
      (value "EL357N(B)(TA)-G")
      (footprint "SOP-4_P2.54")
      (description "贴片光耦")
      (libsource (lib "Miscellaneous Devices LC") (part "EL357N(B)(TA)-G"))
    )
    (comp (ref "U15")
      (value "EL357N(B)(TA)-G")
      (footprint "SOP-4_P2.54")
      (description "贴片光耦")
      (libsource (lib "Miscellaneous Devices LC") (part "EL357N(B)(TA)-G"))
    )
    (comp (ref "U16")
      (value "EL357N(B)(TA)-G")
      (footprint "SOP-4_P2.54")
      (description "贴片光耦")
      (libsource (lib "Miscellaneous Devices LC") (part "EL357N(B)(TA)-G"))
    )
    (comp (ref "U17")
      (value "EL357N(B)(TA)-G")
      (footprint "SOP-4_P2.54")
      (description "贴片光耦")
      (libsource (lib "Miscellaneous Devices LC") (part "EL357N(B)(TA)-G"))
    )
    (comp (ref "U18")
      (value "EL357N(B)(TA)-G")
      (footprint "SOP-4_P2.54")
      (description "贴片光耦")
      (libsource (lib "Miscellaneous Devices LC") (part "EL357N(B)(TA)-G"))
    )
    (comp (ref "U19")
      (value "EL357N(B)(TA)-G")
      (footprint "SOP-4_P2.54")
      (description "贴片光耦")
      (libsource (lib "Miscellaneous Devices LC") (part "EL357N(B)(TA)-G"))
    )
    (comp (ref "U20")
      (value "74HC04")
      (footprint "SOIC-14_150mil")
      (libsource (lib "XCP-SCH_V1.00") (part "74HC04"))
    )
    (comp (ref "U21")
      (value "74HC04")
      (footprint "SOIC-14_150mil")
      (libsource (lib "XCP-SCH_V1.00") (part "74HC04"))
    )
    (comp (ref "U22")
      (value "74HC04")
      (footprint "SOIC-14_150mil")
      (libsource (lib "XCP-SCH_V1.00") (part "74HC04"))
    )
    (comp (ref "U23")
      (value "ULN2803ADW")
      (footprint "SOIC-18_300mil")
      (description "大电流驱动")
      (libsource (lib "Miscellaneous Devices LC") (part "ULN2803ADW"))
    )
    (comp (ref "U24")
      (value "ULN2803ADW")
      (footprint "SOIC-18_300mil")
      (description "大电流驱动")
      (libsource (lib "Miscellaneous Devices LC") (part "ULN2803ADW"))
    )
    (comp (ref "USB1") (value "USB-B") (footprint "USB-b") (libsource (lib "GB-SCH") (part "USB-6")))
    (comp (ref "Y1")
      (value "11.0592MHZ 20PF 20PPM")
      (footprint "SMD-5032_2P")
      (description "贴片晶振")
      (libsource (lib "Miscellaneous Devices LC") (part "SMD-5032_2P 11.0592MHZ 20PF 20PPM"))
    )
  )
  (nets
    (net (code "1") (name "+5V") (class "Default")
      (node (ref "C10") (pin "2") (pinfunction "2_2") (pintype "passive"))
      (node (ref "C13") (pin "2") (pinfunction "2_2") (pintype "passive"))
      (node (ref "C14") (pin "2") (pinfunction "2_2") (pintype "passive"))
      (node (ref "C15") (pin "2") (pinfunction "2_2") (pintype "passive"))
      (node (ref "C16") (pin "2") (pinfunction "2_2") (pintype "passive"))
      (node (ref "C17") (pin "2") (pinfunction "2_2") (pintype "passive"))
      (node (ref "C18") (pin "2") (pinfunction "2_2") (pintype "passive"))
      (node (ref "C2") (pin "2") (pinfunction "2_2") (pintype "passive"))
      (node (ref "C4") (pin "2") (pinfunction "2_2") (pintype "passive"))
      (node (ref "L1") (pin "2") (pinfunction "2_2") (pintype "passive"))
      (node (ref "R1") (pin "2") (pinfunction "2_2") (pintype "passive"))
      (node (ref "R15") (pin "2") (pinfunction "2_2") (pintype "passive"))
      (node (ref "R16") (pin "2") (pinfunction "2_2") (pintype "passive"))
      (node (ref "R17") (pin "1") (pinfunction "1_1") (pintype "passive"))
      (node (ref "R18") (pin "1") (pinfunction "1_1") (pintype "passive"))
      (node (ref "R19") (pin "1") (pinfunction "1_1") (pintype "passive"))
      (node (ref "R20") (pin "1") (pinfunction "1_1") (pintype "passive"))
      (node (ref "R21") (pin "1") (pinfunction "1_1") (pintype "passive"))
      (node (ref "R22") (pin "1") (pinfunction "1_1") (pintype "passive"))
      (node (ref "R23") (pin "1") (pinfunction "1_1") (pintype "passive"))
      (node (ref "R24") (pin "1") (pinfunction "1_1") (pintype "passive"))
      (node (ref "R25") (pin "1") (pinfunction "1_1") (pintype "passive"))
      (node (ref "R26") (pin "1") (pinfunction "1_1") (pintype "passive"))
      (node (ref "R27") (pin "1") (pinfunction "1_1") (pintype "passive"))
      (node (ref "R28") (pin "1") (pinfunction "1_1") (pintype "passive"))
      (node (ref "R29") (pin "1") (pinfunction "1_1") (pintype "passive"))
      (node (ref "R30") (pin "1") (pinfunction "1_1") (pintype "passive"))
      (node (ref "R31") (pin "1") (pinfunction "1_1") (pintype "passive"))
      (node (ref "R32") (pin "1") (pinfunction "1_1") (pintype "passive"))
      (node (ref "R5") (pin "1") (pinfunction "1_1") (pintype "passive"))
      (node (ref "S1") (pin "1") (pinfunction "1_1") (pintype "passive"))
      (node (ref "U2") (pin "38") (pinfunction "VCC_38") (pintype "power_in"))
      (node (ref "U20") (pin "14") (pinfunction "VCC_14") (pintype "passive"))
      (node (ref "U21") (pin "14") (pinfunction "VCC_14") (pintype "passive"))
      (node (ref "U22") (pin "14") (pinfunction "VCC_14") (pintype "passive"))
      (node (ref "U3") (pin "8") (pinfunction "VCC_8") (pintype "passive"))
    )
    (net (code "2") (name "+24V") (class "Default")
      (node (ref "C19") (pin "2") (pinfunction "2_2") (pintype "passive"))
      (node (ref "C20") (pin "2") (pinfunction "2_2") (pintype "passive"))
      (node (ref "C3") (pin "2") (pinfunction "2_2") (pintype "passive"))
      (node (ref "D2") (pin "2") (pinfunction "K_2") (pintype "passive"))
      (node (ref "D24") (pin "A") (pinfunction "A_A") (pintype "passive"))
      (node (ref "D25") (pin "A") (pinfunction "A_A") (pintype "passive"))
      (node (ref "D26") (pin "A") (pinfunction "A_A") (pintype "passive"))
      (node (ref "D27") (pin "A") (pinfunction "A_A") (pintype "passive"))
      (node (ref "D28") (pin "A") (pinfunction "A_A") (pintype "passive"))
      (node (ref "D29") (pin "A") (pinfunction "A_A") (pintype "passive"))
      (node (ref "D30") (pin "A") (pinfunction "A_A") (pintype "passive"))
      (node (ref "D31") (pin "A") (pinfunction "A_A") (pintype "passive"))
      (node (ref "D32") (pin "A") (pinfunction "A_A") (pintype "passive"))
      (node (ref "D33") (pin "A") (pinfunction "A_A") (pintype "passive"))
      (node (ref "D34") (pin "A") (pinfunction "A_A") (pintype "passive"))
      (node (ref "D35") (pin "A") (pinfunction "A_A") (pintype "passive"))
      (node (ref "D36") (pin "A") (pinfunction "A_A") (pintype "passive"))
      (node (ref "D37") (pin "A") (pinfunction "A_A") (pintype "passive"))
      (node (ref "D38") (pin "A") (pinfunction "A_A") (pintype "passive"))
      (node (ref "D39") (pin "A") (pinfunction "A_A") (pintype "passive"))
      (node (ref "P10") (pin "1") (pinfunction "1_1") (pintype "passive"))
      (node (ref "P11") (pin "1") (pinfunction "1_1") (pintype "passive"))
      (node (ref "P12") (pin "1") (pinfunction "1_1") (pintype "passive"))
      (node (ref "P13") (pin "1") (pinfunction "1_1") (pintype "passive"))
      (node (ref "P14") (pin "1") (pinfunction "1_1") (pintype "passive"))
      (node (ref "P15") (pin "1") (pinfunction "1_1") (pintype "passive"))
      (node (ref "P16") (pin "1") (pinfunction "1_1") (pintype "passive"))
      (node (ref "P17") (pin "1") (pinfunction "1_1") (pintype "passive"))
      (node (ref "P18") (pin "1") (pinfunction "1_1") (pintype "passive"))
      (node (ref "P19") (pin "1") (pinfunction "1_1") (pintype "passive"))
      (node (ref "P2") (pin "1") (pinfunction "1_1") (pintype "passive"))
      (node (ref "P20") (pin "1") (pinfunction "1_1") (pintype "passive"))
      (node (ref "P21") (pin "1") (pinfunction "1_1") (pintype "passive"))
      (node (ref "P22") (pin "1") (pinfunction "1_1") (pintype "passive"))
      (node (ref "P23") (pin "1") (pinfunction "1_1") (pintype "passive"))
      (node (ref "P24") (pin "1") (pinfunction "1_1") (pintype "passive"))
      (node (ref "P25") (pin "1") (pinfunction "1_1") (pintype "passive"))
      (node (ref "P26") (pin "1") (pinfunction "1_1") (pintype "passive"))
      (node (ref "P27") (pin "1") (pinfunction "1_1") (pintype "passive"))
      (node (ref "P28") (pin "1") (pinfunction "1_1") (pintype "passive"))
      (node (ref "P29") (pin "1") (pinfunction "1_1") (pintype "passive"))
      (node (ref "P3") (pin "1") (pinfunction "1_1") (pintype "passive"))
      (node (ref "P30") (pin "1") (pinfunction "1_1") (pintype "passive"))
      (node (ref "P31") (pin "1") (pinfunction "1_1") (pintype "passive"))
      (node (ref "P32") (pin "1") (pinfunction "1_1") (pintype "passive"))
      (node (ref "P33") (pin "1") (pinfunction "1_1") (pintype "passive"))
      (node (ref "P4") (pin "1") (pinfunction "1_1") (pintype "passive"))
      (node (ref "P5") (pin "1") (pinfunction "1_1") (pintype "passive"))
      (node (ref "P6") (pin "1") (pinfunction "1_1") (pintype "passive"))
      (node (ref "P7") (pin "1") (pinfunction "1_1") (pintype "passive"))
      (node (ref "P8") (pin "1") (pinfunction "1_1") (pintype "passive"))
      (node (ref "P9") (pin "1") (pinfunction "1_1") (pintype "passive"))
      (node (ref "R3") (pin "1") (pinfunction "1_1") (pintype "passive"))
      (node (ref "R33") (pin "1") (pinfunction "1_1") (pintype "passive"))
      (node (ref "R34") (pin "1") (pinfunction "1_1") (pintype "passive"))
      (node (ref "R35") (pin "1") (pinfunction "1_1") (pintype "passive"))
      (node (ref "R36") (pin "1") (pinfunction "1_1") (pintype "passive"))
      (node (ref "R37") (pin "1") (pinfunction "1_1") (pintype "passive"))
      (node (ref "R38") (pin "1") (pinfunction "1_1") (pintype "passive"))
      (node (ref "R39") (pin "1") (pinfunction "1_1") (pintype "passive"))
      (node (ref "R40") (pin "1") (pinfunction "1_1") (pintype "passive"))
      (node (ref "R41") (pin "1") (pinfunction "1_1") (pintype "passive"))
      (node (ref "R42") (pin "1") (pinfunction "1_1") (pintype "passive"))
      (node (ref "R43") (pin "1") (pinfunction "1_1") (pintype "passive"))
      (node (ref "R44") (pin "1") (pinfunction "1_1") (pintype "passive"))
      (node (ref "R45") (pin "1") (pinfunction "1_1") (pintype "passive"))
      (node (ref "R46") (pin "1") (pinfunction "1_1") (pintype "passive"))
      (node (ref "R47") (pin "1") (pinfunction "1_1") (pintype "passive"))
      (node (ref "R48") (pin "1") (pinfunction "1_1") (pintype "passive"))
      (node (ref "U1") (pin "5") (pinfunction "VIN_5") (pintype "passive"))
      (node (ref "U23") (pin "10") (pinfunction "COM_D_10") (pintype "passive"))
      (node (ref "U24") (pin "10") (pinfunction "COM_D_10") (pintype "passive"))
    )
    (net (code "3") (name "/EARTH") (class "Default")
      (node (ref "C9") (pin "1") (pinfunction "1_1") (pintype "passive"))
      (node (ref "R12") (pin "1") (pinfunction "1_1") (pintype "passive"))
      (node (ref "USB1") (pin "5") (pinfunction "NC_5") (pintype "passive"))
      (node (ref "USB1") (pin "6") (pinfunction "NC_6") (pintype "passive"))
    )
    (net (code "4") (name "/IN1") (class "Default")
      (node (ref "D8") (pin "K") (pinfunction "K_K") (pintype "passive"))
      (node (ref "U2") (pin "31") (pinfunction "P0.6_31") (pintype "passive"))
      (node (ref "U4") (pin "4") (pinfunction "C_4") (pintype "passive"))
    )
    (net (code "5") (name "/IN2") (class "Default")
      (node (ref "D9") (pin "K") (pinfunction "K_K") (pintype "passive"))
      (node (ref "U2") (pin "33") (pinfunction "P0.4_33") (pintype "passive"))
      (node (ref "U5") (pin "4") (pinfunction "C_4") (pintype "passive"))
    )
    (net (code "6") (name "/IN3") (class "Default")
      (node (ref "D10") (pin "K") (pinfunction "K_K") (pintype "passive"))
      (node (ref "U2") (pin "35") (pinfunction "P0.2_35") (pintype "passive"))
      (node (ref "U6") (pin "4") (pinfunction "C_4") (pintype "passive"))
    )
    (net (code "7") (name "/IN4") (class "Default")
      (node (ref "D11") (pin "K") (pinfunction "K_K") (pintype "passive"))
      (node (ref "U2") (pin "37") (pinfunction "P0.0_37") (pintype "passive"))
      (node (ref "U7") (pin "4") (pinfunction "C_4") (pintype "passive"))
    )
    (net (code "8") (name "/IN5") (class "Default")
      (node (ref "D12") (pin "K") (pinfunction "K_K") (pintype "passive"))
      (node (ref "U2") (pin "40") (pinfunction "P1.0_40") (pintype "passive"))
      (node (ref "U8") (pin "4") (pinfunction "C_4") (pintype "passive"))
    )
    (net (code "9") (name "/IN6") (class "Default")
      (node (ref "D13") (pin "K") (pinfunction "K_K") (pintype "passive"))
      (node (ref "U2") (pin "42") (pinfunction "P1.2_42") (pintype "passive"))
      (node (ref "U9") (pin "4") (pinfunction "C_4") (pintype "passive"))
    )
    (net (code "10") (name "/IN7") (class "Default")
      (node (ref "D14") (pin "K") (pinfunction "K_K") (pintype "passive"))
      (node (ref "U10") (pin "4") (pinfunction "C_4") (pintype "passive"))
      (node (ref "U2") (pin "44") (pinfunction "P1.4_44") (pintype "passive"))
    )
    (net (code "11") (name "/IN8") (class "Default")
      (node (ref "D15") (pin "K") (pinfunction "K_K") (pintype "passive"))
      (node (ref "U11") (pin "4") (pinfunction "C_4") (pintype "passive"))
      (node (ref "U2") (pin "2") (pinfunction "P1.6_2") (pintype "passive"))
    )
    (net (code "12") (name "/IN9") (class "Default")
      (node (ref "D16") (pin "K") (pinfunction "K_K") (pintype "passive"))
      (node (ref "U12") (pin "4") (pinfunction "C_4") (pintype "passive"))
      (node (ref "U2") (pin "32") (pinfunction "P0.5_32") (pintype "passive"))
    )
    (net (code "13") (name "/IN10") (class "Default")
      (node (ref "D17") (pin "K") (pinfunction "K_K") (pintype "passive"))
      (node (ref "U13") (pin "4") (pinfunction "C_4") (pintype "passive"))
      (node (ref "U2") (pin "34") (pinfunction "P0.3_34") (pintype "passive"))
    )
    (net (code "14") (name "/IN11") (class "Default")
      (node (ref "D18") (pin "K") (pinfunction "K_K") (pintype "passive"))
      (node (ref "U14") (pin "4") (pinfunction "C_4") (pintype "passive"))
      (node (ref "U2") (pin "36") (pinfunction "P0.1_36") (pintype "passive"))
    )
    (net (code "15") (name "/IN12") (class "Default")
      (node (ref "D19") (pin "K") (pinfunction "K_K") (pintype "passive"))
      (node (ref "U15") (pin "4") (pinfunction "C_4") (pintype "passive"))
      (node (ref "U2") (pin "39") (pinfunction "P4.2_39") (pintype "passive"))
    )
    (net (code "16") (name "/IN13") (class "Default")
      (node (ref "D20") (pin "K") (pinfunction "K_K") (pintype "passive"))
      (node (ref "U16") (pin "4") (pinfunction "C_4") (pintype "passive"))
      (node (ref "U2") (pin "41") (pinfunction "P1.1_41") (pintype "passive"))
    )
    (net (code "17") (name "/IN14") (class "Default")
      (node (ref "D21") (pin "K") (pinfunction "K_K") (pintype "passive"))
      (node (ref "U17") (pin "4") (pinfunction "C_4") (pintype "passive"))
      (node (ref "U2") (pin "43") (pinfunction "P1.3_43") (pintype "passive"))
    )
    (net (code "18") (name "/IN15") (class "Default")
      (node (ref "D22") (pin "K") (pinfunction "K_K") (pintype "passive"))
      (node (ref "U18") (pin "4") (pinfunction "C_4") (pintype "passive"))
      (node (ref "U2") (pin "1") (pinfunction "P1.5_1") (pintype "passive"))
    )
    (net (code "19") (name "/IN16") (class "Default")
      (node (ref "D23") (pin "K") (pinfunction "K_K") (pintype "passive"))
      (node (ref "U19") (pin "4") (pinfunction "C_4") (pintype "passive"))
      (node (ref "U2") (pin "3") (pinfunction "P1.7_3") (pintype "passive"))
    )
    (net (code "20") (name "/INPUT1") (class "Default")
      (node (ref "P2") (pin "2") (pinfunction "2_2") (pintype "passive"))
      (node (ref "U4") (pin "2") (pinfunction "K_2") (pintype "passive"))
    )
    (net (code "21") (name "/INPUT2") (class "Default")
      (node (ref "P3") (pin "2") (pinfunction "2_2") (pintype "passive"))
      (node (ref "U5") (pin "2") (pinfunction "K_2") (pintype "passive"))
    )
    (net (code "22") (name "/INPUT3") (class "Default")
      (node (ref "P4") (pin "2") (pinfunction "2_2") (pintype "passive"))
      (node (ref "U6") (pin "2") (pinfunction "K_2") (pintype "passive"))
    )
    (net (code "23") (name "/INPUT4") (class "Default")
      (node (ref "P5") (pin "2") (pinfunction "2_2") (pintype "passive"))
      (node (ref "U7") (pin "2") (pinfunction "K_2") (pintype "passive"))
    )
    (net (code "24") (name "/INPUT5") (class "Default")
      (node (ref "P6") (pin "2") (pinfunction "2_2") (pintype "passive"))
      (node (ref "U8") (pin "2") (pinfunction "K_2") (pintype "passive"))
    )
    (net (code "25") (name "/INPUT6") (class "Default")
      (node (ref "P7") (pin "2") (pinfunction "2_2") (pintype "passive"))
      (node (ref "U9") (pin "2") (pinfunction "K_2") (pintype "passive"))
    )
    (net (code "26") (name "/INPUT7") (class "Default")
      (node (ref "P8") (pin "2") (pinfunction "2_2") (pintype "passive"))
      (node (ref "U10") (pin "2") (pinfunction "K_2") (pintype "passive"))
    )
    (net (code "27") (name "/INPUT8") (class "Default")
      (node (ref "P9") (pin "2") (pinfunction "2_2") (pintype "passive"))
      (node (ref "U11") (pin "2") (pinfunction "K_2") (pintype "passive"))
    )
    (net (code "28") (name "/INPUT9") (class "Default")
      (node (ref "P10") (pin "2") (pinfunction "2_2") (pintype "passive"))
      (node (ref "U12") (pin "2") (pinfunction "K_2") (pintype "passive"))
    )
    (net (code "29") (name "/INPUT10") (class "Default")
      (node (ref "P11") (pin "2") (pinfunction "2_2") (pintype "passive"))
      (node (ref "U13") (pin "2") (pinfunction "K_2") (pintype "passive"))
    )
    (net (code "30") (name "/INPUT11") (class "Default")
      (node (ref "P12") (pin "2") (pinfunction "2_2") (pintype "passive"))
      (node (ref "U14") (pin "2") (pinfunction "K_2") (pintype "passive"))
    )
    (net (code "31") (name "/INPUT12") (class "Default")
      (node (ref "P13") (pin "2") (pinfunction "2_2") (pintype "passive"))
      (node (ref "U15") (pin "2") (pinfunction "K_2") (pintype "passive"))
    )
    (net (code "32") (name "/INPUT13") (class "Default")
      (node (ref "P14") (pin "2") (pinfunction "2_2") (pintype "passive"))
      (node (ref "U16") (pin "2") (pinfunction "K_2") (pintype "passive"))
    )
    (net (code "33") (name "/INPUT14") (class "Default")
      (node (ref "P15") (pin "2") (pinfunction "2_2") (pintype "passive"))
      (node (ref "U17") (pin "2") (pinfunction "K_2") (pintype "passive"))
    )
    (net (code "34") (name "/INPUT15") (class "Default")
      (node (ref "P16") (pin "2") (pinfunction "2_2") (pintype "passive"))
      (node (ref "U18") (pin "2") (pinfunction "K_2") (pintype "passive"))
    )
    (net (code "35") (name "/INPUT16") (class "Default")
      (node (ref "P17") (pin "2") (pinfunction "2_2") (pintype "passive"))
      (node (ref "U19") (pin "2") (pinfunction "K_2") (pintype "passive"))
    )
    (net (code "36") (name "/LED") (class "Default")
      (node (ref "R14") (pin "2") (pinfunction "2_2") (pintype "passive"))
      (node (ref "U2") (pin "27") (pinfunction "ALE_27") (pintype "passive"))
    )
    (net (code "37") (name "/MCU_RX") (class "Default")
      (node (ref "D5") (pin "1") (pinfunction "A_1") (pintype "passive"))
      (node (ref "U2") (pin "5") (pinfunction "P3.0/RXD_5") (pintype "passive"))
    )
    (net (code "38") (name "/MCU_TX") (class "Default")
      (node (ref "R10") (pin "1") (pinfunction "1_1") (pintype "passive"))
      (node (ref "U2") (pin "7") (pinfunction "P3.1/TXD_7") (pintype "passive"))
    )
    (net (code "39") (name "/O1") (class "Default")
      (node (ref "U20") (pin "8") (pinfunction "4Y_8") (pintype "passive"))
      (node (ref "U23") (pin "1") (pinfunction "IN1_1") (pintype "input"))
    )
    (net (code "40") (name "/O2") (class "Default")
      (node (ref "U20") (pin "12") (pinfunction "6Y_12") (pintype "passive"))
      (node (ref "U23") (pin "3") (pinfunction "IN3_3") (pintype "input"))
    )
    (net (code "41") (name "/O3") (class "Default")
      (node (ref "U21") (pin "2") (pinfunction "1Y_2") (pintype "passive"))
      (node (ref "U23") (pin "5") (pinfunction "IN5_5") (pintype "input"))
    )
    (net (code "42") (name "/O4") (class "Default")
      (node (ref "U20") (pin "4") (pinfunction "2Y_4") (pintype "passive"))
      (node (ref "U23") (pin "7") (pinfunction "IN7_7") (pintype "input"))
    )
    (net (code "43") (name "/O5") (class "Default")
      (node (ref "U22") (pin "6") (pinfunction "3Y_6") (pintype "passive"))
      (node (ref "U24") (pin "1") (pinfunction "IN1_1") (pintype "input"))
    )
    (net (code "44") (name "/O6") (class "Default")
      (node (ref "U21") (pin "8") (pinfunction "4Y_8") (pintype "passive"))
      (node (ref "U24") (pin "3") (pinfunction "IN3_3") (pintype "input"))
    )
    (net (code "45") (name "/O7") (class "Default")
      (node (ref "U21") (pin "12") (pinfunction "6Y_12") (pintype "passive"))
      (node (ref "U24") (pin "5") (pinfunction "IN5_5") (pintype "input"))
    )
    (net (code "46") (name "/O8") (class "Default")
      (node (ref "U22") (pin "10") (pinfunction "5Y_10") (pintype "passive"))
      (node (ref "U24") (pin "7") (pinfunction "IN7_7") (pintype "input"))
    )
    (net (code "47") (name "/O9") (class "Default")
      (node (ref "U20") (pin "10") (pinfunction "5Y_10") (pintype "passive"))
      (node (ref "U23") (pin "2") (pinfunction "IN2_2") (pintype "input"))
    )
    (net (code "48") (name "/O10") (class "Default")
      (node (ref "U21") (pin "4") (pinfunction "2Y_4") (pintype "passive"))
      (node (ref "U23") (pin "4") (pinfunction "IN4_4") (pintype "input"))
    )
    (net (code "49") (name "/O11") (class "Default")
      (node (ref "U20") (pin "6") (pinfunction "3Y_6") (pintype "passive"))
      (node (ref "U23") (pin "6") (pinfunction "IN6_6") (pintype "input"))
    )
    (net (code "50") (name "/O12") (class "Default")
      (node (ref "U20") (pin "2") (pinfunction "1Y_2") (pintype "passive"))
      (node (ref "U23") (pin "8") (pinfunction "IN8_8") (pintype "input"))
    )
    (net (code "51") (name "/O13") (class "Default")
      (node (ref "U21") (pin "6") (pinfunction "3Y_6") (pintype "passive"))
      (node (ref "U24") (pin "2") (pinfunction "IN2_2") (pintype "input"))
    )
    (net (code "52") (name "/O14") (class "Default")
      (node (ref "U21") (pin "10") (pinfunction "5Y_10") (pintype "passive"))
      (node (ref "U24") (pin "4") (pinfunction "IN4_4") (pintype "input"))
    )
    (net (code "53") (name "/O15") (class "Default")
      (node (ref "U22") (pin "8") (pinfunction "4Y_8") (pintype "passive"))
      (node (ref "U24") (pin "6") (pinfunction "IN6_6") (pintype "input"))
    )
    (net (code "54") (name "/O16") (class "Default")
      (node (ref "U22") (pin "12") (pinfunction "6Y_12") (pintype "passive"))
      (node (ref "U24") (pin "8") (pinfunction "IN8_8") (pintype "input"))
    )
    (net (code "55") (name "/OUT1") (class "Default")
      (node (ref "U2") (pin "20") (pinfunction "P2.2_20") (pintype "passive"))
      (node (ref "U20") (pin "9") (pinfunction "4A_9") (pintype "passive"))
    )
    (net (code "56") (name "/OUT2") (class "Default")
      (node (ref "U2") (pin "22") (pinfunction "P2.4_22") (pintype "passive"))
      (node (ref "U20") (pin "13") (pinfunction "6A_13") (pintype "passive"))
    )
    (net (code "57") (name "/OUT3") (class "Default")
      (node (ref "U2") (pin "19") (pinfunction "P2.1_19") (pintype "passive"))
      (node (ref "U21") (pin "1") (pinfunction "1A_1") (pintype "passive"))
    )
    (net (code "58") (name "/OUT4") (class "Default")
      (node (ref "U2") (pin "24") (pinfunction "P2.6_24") (pintype "passive"))
      (node (ref "U20") (pin "3") (pinfunction "2A_3") (pintype "passive"))
    )
    (net (code "59") (name "/OUT5") (class "Default")
      (node (ref "U2") (pin "6") (pinfunction "P4.3_6") (pintype "passive"))
      (node (ref "U22") (pin "5") (pinfunction "3A_5") (pintype "passive"))
    )
    (net (code "60") (name "/OUT6") (class "Default")
      (node (ref "U2") (pin "11") (pinfunction "P3.5_11") (pintype "passive"))
      (node (ref "U21") (pin "9") (pinfunction "4A_9") (pintype "passive"))
    )
    (net (code "61") (name "/OUT7") (class "Default")
      (node (ref "U2") (pin "13") (pinfunction "P3.7_13") (pintype "passive"))
      (node (ref "U21") (pin "13") (pinfunction "6A_13") (pintype "passive"))
    )
    (net (code "62") (name "/OUT8") (class "Default")
      (node (ref "U2") (pin "9") (pinfunction "P3.3_9") (pintype "passive"))
      (node (ref "U22") (pin "11") (pinfunction "5A_11") (pintype "passive"))
    )
    (net (code "63") (name "/OUT9") (class "Default")
      (node (ref "U2") (pin "21") (pinfunction "P2.3_21") (pintype "passive"))
      (node (ref "U20") (pin "11") (pinfunction "5A_11") (pintype "passive"))
    )
    (net (code "64") (name "/OUT10") (class "Default")
      (node (ref "U2") (pin "18") (pinfunction "P2.0_18") (pintype "passive"))
      (node (ref "U21") (pin "3") (pinfunction "2A_3") (pintype "passive"))
    )
    (net (code "65") (name "/OUT11") (class "Default")
      (node (ref "U2") (pin "23") (pinfunction "P2.5_23") (pintype "passive"))
      (node (ref "U20") (pin "5") (pinfunction "3A_5") (pintype "passive"))
    )
    (net (code "66") (name "/OUT12") (class "Default")
      (node (ref "U2") (pin "25") (pinfunction "P2.7_25") (pintype "passive"))
      (node (ref "U20") (pin "1") (pinfunction "1A_1") (pintype "passive"))
    )
    (net (code "67") (name "/OUT13") (class "Default")
      (node (ref "U2") (pin "17") (pinfunction "P4.0_17") (pintype "passive"))
      (node (ref "U21") (pin "5") (pinfunction "3A_5") (pintype "passive"))
    )
    (net (code "68") (name "/OUT14") (class "Default")
      (node (ref "U2") (pin "12") (pinfunction "P3.6_12") (pintype "passive"))
      (node (ref "U21") (pin "11") (pinfunction "5A_11") (pintype "passive"))
    )
    (net (code "69") (name "/OUT15") (class "Default")
      (node (ref "U2") (pin "8") (pinfunction "P3.2_8") (pintype "passive"))
      (node (ref "U22") (pin "9") (pinfunction "4A_9") (pintype "passive"))
    )
    (net (code "70") (name "/OUT16") (class "Default")
      (node (ref "U2") (pin "10") (pinfunction "P3.4_10") (pintype "passive"))
      (node (ref "U22") (pin "13") (pinfunction "6A_13") (pintype "passive"))
    )
    (net (code "71") (name "/OUTPUT1") (class "Default")
      (node (ref "P18") (pin "2") (pinfunction "2_2") (pintype "passive"))
      (node (ref "R6") (pin "1") (pinfunction "1_1") (pintype "passive"))
      (node (ref "U23") (pin "18") (pinfunction "OUT1_18") (pintype "open_collector"))
    )
    (net (code "72") (name "/OUTPUT2") (class "Default")
      (node (ref "P19") (pin "2") (pinfunction "2_2") (pintype "passive"))
      (node (ref "R49") (pin "1") (pinfunction "1_1") (pintype "passive"))
      (node (ref "U23") (pin "16") (pinfunction "OUT3_16") (pintype "open_collector"))
    )
    (net (code "73") (name "/OUTPUT3") (class "Default")
      (node (ref "P20") (pin "2") (pinfunction "2_2") (pintype "passive"))
      (node (ref "R51") (pin "1") (pinfunction "1_1") (pintype "passive"))
      (node (ref "U23") (pin "14") (pinfunction "OUT5_14") (pintype "open_collector"))
    )
    (net (code "74") (name "/OUTPUT4") (class "Default")
      (node (ref "P21") (pin "2") (pinfunction "2_2") (pintype "passive"))
      (node (ref "R53") (pin "1") (pinfunction "1_1") (pintype "passive"))
      (node (ref "U23") (pin "12") (pinfunction "OUT7_12") (pintype "open_collector"))
    )
    (net (code "75") (name "/OUTPUT5") (class "Default")
      (node (ref "P22") (pin "2") (pinfunction "2_2") (pintype "passive"))
      (node (ref "R55") (pin "1") (pinfunction "1_1") (pintype "passive"))
      (node (ref "U24") (pin "18") (pinfunction "OUT1_18") (pintype "open_collector"))
    )
    (net (code "76") (name "/OUTPUT6") (class "Default")
      (node (ref "P23") (pin "2") (pinfunction "2_2") (pintype "passive"))
      (node (ref "R57") (pin "1") (pinfunction "1_1") (pintype "passive"))
      (node (ref "U24") (pin "16") (pinfunction "OUT3_16") (pintype "open_collector"))
    )
    (net (code "77") (name "/OUTPUT7") (class "Default")
      (node (ref "P24") (pin "2") (pinfunction "2_2") (pintype "passive"))
      (node (ref "R59") (pin "1") (pinfunction "1_1") (pintype "passive"))
      (node (ref "U24") (pin "14") (pinfunction "OUT5_14") (pintype "open_collector"))
    )
    (net (code "78") (name "/OUTPUT8") (class "Default")
      (node (ref "P25") (pin "2") (pinfunction "2_2") (pintype "passive"))
      (node (ref "R61") (pin "1") (pinfunction "1_1") (pintype "passive"))
      (node (ref "U24") (pin "12") (pinfunction "OUT7_12") (pintype "open_collector"))
    )
    (net (code "79") (name "/OUTPUT9") (class "Default")
      (node (ref "P26") (pin "2") (pinfunction "2_2") (pintype "passive"))
      (node (ref "R7") (pin "1") (pinfunction "1_1") (pintype "passive"))
      (node (ref "U23") (pin "17") (pinfunction "OUT2_17") (pintype "open_collector"))
    )
    (net (code "80") (name "/OUTPUT10") (class "Default")
      (node (ref "P27") (pin "2") (pinfunction "2_2") (pintype "passive"))
      (node (ref "R50") (pin "1") (pinfunction "1_1") (pintype "passive"))
      (node (ref "U23") (pin "15") (pinfunction "OUT4_15") (pintype "open_collector"))
    )
    (net (code "81") (name "/OUTPUT11") (class "Default")
      (node (ref "P28") (pin "2") (pinfunction "2_2") (pintype "passive"))
      (node (ref "R52") (pin "1") (pinfunction "1_1") (pintype "passive"))
      (node (ref "U23") (pin "13") (pinfunction "OUT6_13") (pintype "open_collector"))
    )
    (net (code "82") (name "/OUTPUT12") (class "Default")
      (node (ref "P29") (pin "2") (pinfunction "2_2") (pintype "passive"))
      (node (ref "R54") (pin "1") (pinfunction "1_1") (pintype "passive"))
      (node (ref "U23") (pin "11") (pinfunction "OUT8_11") (pintype "open_collector"))
    )
    (net (code "83") (name "/OUTPUT13") (class "Default")
      (node (ref "P30") (pin "2") (pinfunction "2_2") (pintype "passive"))
      (node (ref "R56") (pin "1") (pinfunction "1_1") (pintype "passive"))
      (node (ref "U24") (pin "17") (pinfunction "OUT2_17") (pintype "open_collector"))
    )
    (net (code "84") (name "/OUTPUT14") (class "Default")
      (node (ref "P31") (pin "2") (pinfunction "2_2") (pintype "passive"))
      (node (ref "R58") (pin "1") (pinfunction "1_1") (pintype "passive"))
      (node (ref "U24") (pin "15") (pinfunction "OUT4_15") (pintype "open_collector"))
    )
    (net (code "85") (name "/OUTPUT15") (class "Default")
      (node (ref "P32") (pin "2") (pinfunction "2_2") (pintype "passive"))
      (node (ref "R60") (pin "1") (pinfunction "1_1") (pintype "passive"))
      (node (ref "U24") (pin "13") (pinfunction "OUT6_13") (pintype "open_collector"))
    )
    (net (code "86") (name "/OUTPUT16") (class "Default")
      (node (ref "P33") (pin "2") (pinfunction "2_2") (pintype "passive"))
      (node (ref "R62") (pin "1") (pinfunction "1_1") (pintype "passive"))
      (node (ref "U24") (pin "11") (pinfunction "OUT8_11") (pintype "open_collector"))
    )
    (net (code "87") (name "/RST") (class "Default")
      (node (ref "C10") (pin "1") (pinfunction "1_1") (pintype "passive"))
      (node (ref "R13") (pin "1") (pinfunction "1_1") (pintype "passive"))
      (node (ref "S1") (pin "2") (pinfunction "2_2") (pintype "passive"))
      (node (ref "U2") (pin "4") (pinfunction "RST_4") (pintype "passive"))
    )
    (net (code "88") (name "/SCL") (class "Default")
      (node (ref "R15") (pin "1") (pinfunction "1_1") (pintype "passive"))
      (node (ref "U2") (pin "28") (pinfunction "P4.1_28") (pintype "passive"))
      (node (ref "U3") (pin "6") (pinfunction "SCL_6") (pintype "passive"))
    )
    (net (code "89") (name "/SDA") (class "Default")
      (node (ref "R16") (pin "1") (pinfunction "1_1") (pintype "passive"))
      (node (ref "U2") (pin "30") (pinfunction "P0.7_30") (pintype "passive"))
      (node (ref "U3") (pin "5") (pinfunction "SDA_5") (pintype "passive"))
    )
    (net (code "90") (name "/USB_D+") (class "Default")
      (node (ref "IC1") (pin "15") (pinfunction "USBDP_15") (pintype "passive"))
      (node (ref "USB1") (pin "3") (pinfunction "USB+_3") (pintype "passive"))
    )
    (net (code "91") (name "/USB_D-") (class "Default")
      (node (ref "IC1") (pin "16") (pinfunction "USBDM_16") (pintype "passive"))
      (node (ref "USB1") (pin "2") (pinfunction "USB-_2") (pintype "passive"))
    )
    (net (code "92") (name "/USB_VBUS") (class "Default")
      (node (ref "L2") (pin "2") (pinfunction "2_2") (pintype "passive"))
      (node (ref "USB1") (pin "1") (pinfunction "VCC_1") (pintype "passive"))
    )
    (net (code "93") (name "/VCCIO") (class "Default")
      (node (ref "C7") (pin "2") (pinfunction "2_2") (pintype "passive"))
      (node (ref "IC1") (pin "17") (pinfunction "3V3OUT_17") (pintype "passive"))
      (node (ref "IC1") (pin "4") (pinfunction "VCCIO_4") (pintype "passive"))
    )
    (net (code "94") (name "/XTAL1") (class "Default")
      (node (ref "C12") (pin "1") (pinfunction "1_1") (pintype "passive"))
      (node (ref "U2") (pin "15") (pinfunction "XTAL1_15") (pintype "passive"))
      (node (ref "Y1") (pin "1") (pinfunction "OSC1_1") (pintype "passive"))
    )
    (net (code "95") (name "/XTAL2") (class "Default")
      (node (ref "C11") (pin "1") (pinfunction "1_1") (pintype "passive"))
      (node (ref "U2") (pin "14") (pinfunction "XTAL2_14") (pintype "passive"))
      (node (ref "Y1") (pin "2") (pinfunction "OSC2_2") (pintype "passive"))
    )
    (net (code "96") (name "GND") (class "Default")
      (node (ref "C11") (pin "2") (pinfunction "2_2") (pintype "passive"))
      (node (ref "C12") (pin "2") (pinfunction "2_2") (pintype "passive"))
      (node (ref "C13") (pin "1") (pinfunction "1_1") (pintype "passive"))
      (node (ref "C14") (pin "1") (pinfunction "1_1") (pintype "passive"))
      (node (ref "C15") (pin "1") (pinfunction "1_1") (pintype "passive"))
      (node (ref "C16") (pin "1") (pinfunction "1_1") (pintype "passive"))
      (node (ref "C17") (pin "1") (pinfunction "1_1") (pintype "passive"))
      (node (ref "C18") (pin "1") (pinfunction "1_1") (pintype "passive"))
      (node (ref "C19") (pin "1") (pinfunction "1_1") (pintype "passive"))
      (node (ref "C2") (pin "1") (pinfunction "1_1") (pintype "passive"))
      (node (ref "C20") (pin "1") (pinfunction "1_1") (pintype "passive"))
      (node (ref "C3") (pin "1") (pinfunction "1_1") (pintype "passive"))
      (node (ref "C5") (pin "1") (pinfunction "1_1") (pintype "passive"))
      (node (ref "C6") (pin "1") (pinfunction "1_1") (pintype "passive"))
      (node (ref "C7") (pin "1") (pinfunction "1_1") (pintype "passive"))
      (node (ref "C8") (pin "1") (pinfunction "1_1") (pintype "passive"))
      (node (ref "C9") (pin "2") (pinfunction "2_2") (pintype "passive"))
      (node (ref "D1") (pin "1") (pinfunction "A_1") (pintype "passive"))
      (node (ref "D3") (pin "K") (pinfunction "K_K") (pintype "passive"))
      (node (ref "D7") (pin "K") (pinfunction "K_K") (pintype "passive"))
      (node (ref "IC1") (pin "18") (pinfunction "GND_18") (pintype "passive"))
      (node (ref "IC1") (pin "21") (pinfunction "GND_21") (pintype "passive"))
      (node (ref "IC1") (pin "25") (pinfunction "AGND_25") (pintype "passive"))
      (node (ref "IC1") (pin "26") (pinfunction "TEST_26") (pintype "passive"))
      (node (ref "IC1") (pin "7") (pinfunction "GND_7") (pintype "passive"))
      (node (ref "P1") (pin "1") (pinfunction "1_1") (pintype "passive"))
      (node (ref "P10") (pin "3") (pinfunction "3_3") (pintype "passive"))
      (node (ref "P11") (pin "3") (pinfunction "3_3") (pintype "passive"))
      (node (ref "P12") (pin "3") (pinfunction "3_3") (pintype "passive"))
      (node (ref "P13") (pin "3") (pinfunction "3_3") (pintype "passive"))
      (node (ref "P14") (pin "3") (pinfunction "3_3") (pintype "passive"))
      (node (ref "P15") (pin "3") (pinfunction "3_3") (pintype "passive"))
      (node (ref "P16") (pin "3") (pinfunction "3_3") (pintype "passive"))
      (node (ref "P17") (pin "3") (pinfunction "3_3") (pintype "passive"))
      (node (ref "P2") (pin "3") (pinfunction "3_3") (pintype "passive"))
      (node (ref "P3") (pin "3") (pinfunction "3_3") (pintype "passive"))
      (node (ref "P4") (pin "3") (pinfunction "3_3") (pintype "passive"))
      (node (ref "P5") (pin "3") (pinfunction "3_3") (pintype "passive"))
      (node (ref "P6") (pin "3") (pinfunction "3_3") (pintype "passive"))
      (node (ref "P7") (pin "3") (pinfunction "3_3") (pintype "passive"))
      (node (ref "P8") (pin "3") (pinfunction "3_3") (pintype "passive"))
      (node (ref "P9") (pin "3") (pinfunction "3_3") (pintype "passive"))
      (node (ref "R12") (pin "2") (pinfunction "2_2") (pintype "passive"))
      (node (ref "R13") (pin "2") (pinfunction "2_2") (pintype "passive"))
      (node (ref "R2") (pin "2") (pinfunction "2_2") (pintype "passive"))
      (node (ref "R4") (pin "2") (pinfunction "2_2") (pintype "passive"))
      (node (ref "U1") (pin "2") (pinfunction "GND_2") (pintype "passive"))
      (node (ref "U10") (pin "3") (pinfunction "E_3") (pintype "passive"))
      (node (ref "U11") (pin "3") (pinfunction "E_3") (pintype "passive"))
      (node (ref "U12") (pin "3") (pinfunction "E_3") (pintype "passive"))
      (node (ref "U13") (pin "3") (pinfunction "E_3") (pintype "passive"))
      (node (ref "U14") (pin "3") (pinfunction "E_3") (pintype "passive"))
      (node (ref "U15") (pin "3") (pinfunction "E_3") (pintype "passive"))
      (node (ref "U16") (pin "3") (pinfunction "E_3") (pintype "passive"))
      (node (ref "U17") (pin "3") (pinfunction "E_3") (pintype "passive"))
      (node (ref "U18") (pin "3") (pinfunction "E_3") (pintype "passive"))
      (node (ref "U19") (pin "3") (pinfunction "E_3") (pintype "passive"))
      (node (ref "U2") (pin "16") (pinfunction "GND_16") (pintype "power_in"))
      (node (ref "U20") (pin "7") (pinfunction "GND_7") (pintype "passive"))
      (node (ref "U21") (pin "7") (pinfunction "GND_7") (pintype "passive"))
      (node (ref "U22") (pin "7") (pinfunction "GND_7") (pintype "passive"))
      (node (ref "U23") (pin "9") (pinfunction "GND_9") (pintype "power_in"))
      (node (ref "U24") (pin "9") (pinfunction "GND_9") (pintype "power_in"))
      (node (ref "U3") (pin "1") (pinfunction "A0_1") (pintype "passive"))
      (node (ref "U3") (pin "2") (pinfunction "A1_2") (pintype "passive"))
      (node (ref "U3") (pin "3") (pinfunction "A3_3") (pintype "passive"))
      (node (ref "U3") (pin "4") (pinfunction "GND_4") (pintype "passive"))
      (node (ref "U3") (pin "7") (pinfunction "WP_7") (pintype "passive"))
      (node (ref "U4") (pin "3") (pinfunction "E_3") (pintype "passive"))
      (node (ref "U5") (pin "3") (pinfunction "E_3") (pintype "passive"))
      (node (ref "U6") (pin "3") (pinfunction "E_3") (pintype "passive"))
      (node (ref "U7") (pin "3") (pinfunction "E_3") (pintype "passive"))
      (node (ref "U8") (pin "3") (pinfunction "E_3") (pintype "passive"))
      (node (ref "U9") (pin "3") (pinfunction "E_3") (pintype "passive"))
      (node (ref "USB1") (pin "4") (pinfunction "GND_4") (pintype "passive"))
    )
    (net (code "97") (name "Net-(D1-K)") (class "Default")
      (node (ref "C1") (pin "1") (pinfunction "1_1") (pintype "passive"))
      (node (ref "D1") (pin "2") (pinfunction "K_2") (pintype "passive"))
      (node (ref "L1") (pin "1") (pinfunction "1_1") (pintype "passive"))
      (node (ref "U1") (pin "6") (pinfunction "SW_6") (pintype "passive"))
    )
    (net (code "98") (name "Net-(D3-PadA)") (class "Default")
      (node (ref "D3") (pin "A") (pinfunction "A_A") (pintype "passive"))
      (node (ref "R1") (pin "1") (pinfunction "1_1") (pintype "passive"))
    )
    (net (code "99") (name "Net-(D4-PadK)") (class "Default")
      (node (ref "D4") (pin "K") (pinfunction "K_K") (pintype "passive"))
      (node (ref "R8") (pin "2") (pinfunction "2_2") (pintype "passive"))
    )
    (net (code "100") (name "Net-(D5-K)") (class "Default")
      (node (ref "D5") (pin "2") (pinfunction "K_2") (pintype "passive"))
      (node (ref "IC1") (pin "1") (pinfunction "TXD_1") (pintype "passive"))
    )
    (net (code "101") (name "Net-(D6-PadK)") (class "Default")
      (node (ref "D6") (pin "K") (pinfunction "K_K") (pintype "passive"))
      (node (ref "R9") (pin "2") (pinfunction "2_2") (pintype "passive"))
    )
    (net (code "102") (name "Net-(D7-PadA)") (class "Default")
      (node (ref "D7") (pin "A") (pinfunction "A_A") (pintype "passive"))
      (node (ref "R14") (pin "1") (pinfunction "1_1") (pintype "passive"))
    )
    (net (code "103") (name "Net-(D8-PadA)") (class "Default")
      (node (ref "D8") (pin "A") (pinfunction "A_A") (pintype "passive"))
      (node (ref "R17") (pin "2") (pinfunction "2_2") (pintype "passive"))
    )
    (net (code "104") (name "Net-(D9-PadA)") (class "Default")
      (node (ref "D9") (pin "A") (pinfunction "A_A") (pintype "passive"))
      (node (ref "R18") (pin "2") (pinfunction "2_2") (pintype "passive"))
    )
    (net (code "105") (name "Net-(D10-PadA)") (class "Default")
      (node (ref "D10") (pin "A") (pinfunction "A_A") (pintype "passive"))
      (node (ref "R19") (pin "2") (pinfunction "2_2") (pintype "passive"))
    )
    (net (code "106") (name "Net-(D11-PadA)") (class "Default")
      (node (ref "D11") (pin "A") (pinfunction "A_A") (pintype "passive"))
      (node (ref "R20") (pin "2") (pinfunction "2_2") (pintype "passive"))
    )
    (net (code "107") (name "Net-(D12-PadA)") (class "Default")
      (node (ref "D12") (pin "A") (pinfunction "A_A") (pintype "passive"))
      (node (ref "R21") (pin "2") (pinfunction "2_2") (pintype "passive"))
    )
    (net (code "108") (name "Net-(D13-PadA)") (class "Default")
      (node (ref "D13") (pin "A") (pinfunction "A_A") (pintype "passive"))
      (node (ref "R22") (pin "2") (pinfunction "2_2") (pintype "passive"))
    )
    (net (code "109") (name "Net-(D14-PadA)") (class "Default")
      (node (ref "D14") (pin "A") (pinfunction "A_A") (pintype "passive"))
      (node (ref "R23") (pin "2") (pinfunction "2_2") (pintype "passive"))
    )
    (net (code "110") (name "Net-(D15-PadA)") (class "Default")
      (node (ref "D15") (pin "A") (pinfunction "A_A") (pintype "passive"))
      (node (ref "R24") (pin "2") (pinfunction "2_2") (pintype "passive"))
    )
    (net (code "111") (name "Net-(D16-PadA)") (class "Default")
      (node (ref "D16") (pin "A") (pinfunction "A_A") (pintype "passive"))
      (node (ref "R25") (pin "2") (pinfunction "2_2") (pintype "passive"))
    )
    (net (code "112") (name "Net-(D17-PadA)") (class "Default")
      (node (ref "D17") (pin "A") (pinfunction "A_A") (pintype "passive"))
      (node (ref "R26") (pin "2") (pinfunction "2_2") (pintype "passive"))
    )
    (net (code "113") (name "Net-(D18-PadA)") (class "Default")
      (node (ref "D18") (pin "A") (pinfunction "A_A") (pintype "passive"))
      (node (ref "R27") (pin "2") (pinfunction "2_2") (pintype "passive"))
    )
    (net (code "114") (name "Net-(D19-PadA)") (class "Default")
      (node (ref "D19") (pin "A") (pinfunction "A_A") (pintype "passive"))
      (node (ref "R28") (pin "2") (pinfunction "2_2") (pintype "passive"))
    )
    (net (code "115") (name "Net-(D20-PadA)") (class "Default")
      (node (ref "D20") (pin "A") (pinfunction "A_A") (pintype "passive"))
      (node (ref "R29") (pin "2") (pinfunction "2_2") (pintype "passive"))
    )
    (net (code "116") (name "Net-(D21-PadA)") (class "Default")
      (node (ref "D21") (pin "A") (pinfunction "A_A") (pintype "passive"))
      (node (ref "R30") (pin "2") (pinfunction "2_2") (pintype "passive"))
    )
    (net (code "117") (name "Net-(D22-PadA)") (class "Default")
      (node (ref "D22") (pin "A") (pinfunction "A_A") (pintype "passive"))
      (node (ref "R31") (pin "2") (pinfunction "2_2") (pintype "passive"))
    )
    (net (code "118") (name "Net-(D23-PadA)") (class "Default")
      (node (ref "D23") (pin "A") (pinfunction "A_A") (pintype "passive"))
      (node (ref "R32") (pin "2") (pinfunction "2_2") (pintype "passive"))
    )
    (net (code "119") (name "Net-(D24-PadK)") (class "Default")
      (node (ref "D24") (pin "K") (pinfunction "K_K") (pintype "passive"))
      (node (ref "R6") (pin "2") (pinfunction "2_2") (pintype "passive"))
    )
    (net (code "120") (name "Net-(D25-PadK)") (class "Default")
      (node (ref "D25") (pin "K") (pinfunction "K_K") (pintype "passive"))
      (node (ref "R7") (pin "2") (pinfunction "2_2") (pintype "passive"))
    )
    (net (code "121") (name "Net-(D26-PadK)") (class "Default")
      (node (ref "D26") (pin "K") (pinfunction "K_K") (pintype "passive"))
      (node (ref "R49") (pin "2") (pinfunction "2_2") (pintype "passive"))
    )
    (net (code "122") (name "Net-(D27-PadK)") (class "Default")
      (node (ref "D27") (pin "K") (pinfunction "K_K") (pintype "passive"))
      (node (ref "R50") (pin "2") (pinfunction "2_2") (pintype "passive"))
    )
    (net (code "123") (name "Net-(D28-PadK)") (class "Default")
      (node (ref "D28") (pin "K") (pinfunction "K_K") (pintype "passive"))
      (node (ref "R51") (pin "2") (pinfunction "2_2") (pintype "passive"))
    )
    (net (code "124") (name "Net-(D29-PadK)") (class "Default")
      (node (ref "D29") (pin "K") (pinfunction "K_K") (pintype "passive"))
      (node (ref "R52") (pin "2") (pinfunction "2_2") (pintype "passive"))
    )
    (net (code "125") (name "Net-(D30-PadK)") (class "Default")
      (node (ref "D30") (pin "K") (pinfunction "K_K") (pintype "passive"))
      (node (ref "R53") (pin "2") (pinfunction "2_2") (pintype "passive"))
    )
    (net (code "126") (name "Net-(D31-PadK)") (class "Default")
      (node (ref "D31") (pin "K") (pinfunction "K_K") (pintype "passive"))
      (node (ref "R54") (pin "2") (pinfunction "2_2") (pintype "passive"))
    )
    (net (code "127") (name "Net-(D32-PadK)") (class "Default")
      (node (ref "D32") (pin "K") (pinfunction "K_K") (pintype "passive"))
      (node (ref "R55") (pin "2") (pinfunction "2_2") (pintype "passive"))
    )
    (net (code "128") (name "Net-(D33-PadK)") (class "Default")
      (node (ref "D33") (pin "K") (pinfunction "K_K") (pintype "passive"))
      (node (ref "R56") (pin "2") (pinfunction "2_2") (pintype "passive"))
    )
    (net (code "129") (name "Net-(D34-PadK)") (class "Default")
      (node (ref "D34") (pin "K") (pinfunction "K_K") (pintype "passive"))
      (node (ref "R57") (pin "2") (pinfunction "2_2") (pintype "passive"))
    )
    (net (code "130") (name "Net-(D35-PadK)") (class "Default")
      (node (ref "D35") (pin "K") (pinfunction "K_K") (pintype "passive"))
      (node (ref "R58") (pin "2") (pinfunction "2_2") (pintype "passive"))
    )
    (net (code "131") (name "Net-(D36-PadK)") (class "Default")
      (node (ref "D36") (pin "K") (pinfunction "K_K") (pintype "passive"))
      (node (ref "R59") (pin "2") (pinfunction "2_2") (pintype "passive"))
    )
    (net (code "132") (name "Net-(D37-PadK)") (class "Default")
      (node (ref "D37") (pin "K") (pinfunction "K_K") (pintype "passive"))
      (node (ref "R60") (pin "2") (pinfunction "2_2") (pintype "passive"))
    )
    (net (code "133") (name "Net-(D38-PadK)") (class "Default")
      (node (ref "D38") (pin "K") (pinfunction "K_K") (pintype "passive"))
      (node (ref "R61") (pin "2") (pinfunction "2_2") (pintype "passive"))
    )
    (net (code "134") (name "Net-(D39-PadK)") (class "Default")
      (node (ref "D39") (pin "K") (pinfunction "K_K") (pintype "passive"))
      (node (ref "R62") (pin "2") (pinfunction "2_2") (pintype "passive"))
    )
    (net (code "135") (name "Net-(IC1-CBUS0)") (class "Default")
      (node (ref "IC1") (pin "23") (pinfunction "CBUS0_23") (pintype "passive"))
      (node (ref "R8") (pin "1") (pinfunction "1_1") (pintype "passive"))
    )
    (net (code "136") (name "Net-(IC1-CBUS1)") (class "Default")
      (node (ref "IC1") (pin "22") (pinfunction "CBUS1_22") (pintype "passive"))
      (node (ref "R9") (pin "1") (pinfunction "1_1") (pintype "passive"))
    )
    (net (code "137") (name "Net-(IC1-RESET#)") (class "Default")
      (node (ref "C8") (pin "2") (pinfunction "2_2") (pintype "passive"))
      (node (ref "IC1") (pin "19") (pinfunction "RESET#_19") (pintype "passive"))
      (node (ref "R11") (pin "1") (pinfunction "1_1") (pintype "passive"))
    )
    (net (code "138") (name "Net-(IC1-RXD)") (class "Default")
      (node (ref "IC1") (pin "5") (pinfunction "RXD_5") (pintype "passive"))
      (node (ref "R10") (pin "2") (pinfunction "2_2") (pintype "passive"))
    )
    (net (code "139") (name "Net-(IC1-VCC)") (class "Default")
      (node (ref "C5") (pin "2") (pinfunction "2_2") (pintype "passive"))
      (node (ref "C6") (pin "2") (pinfunction "2_2") (pintype "passive"))
      (node (ref "D4") (pin "A") (pinfunction "A_A") (pintype "passive"))
      (node (ref "D6") (pin "A") (pinfunction "A_A") (pintype "passive"))
      (node (ref "IC1") (pin "20") (pinfunction "VCC_20") (pintype "passive"))
      (node (ref "L2") (pin "1") (pinfunction "1_1") (pintype "passive"))
      (node (ref "R11") (pin "2") (pinfunction "2_2") (pintype "passive"))
    )
    (net (code "140") (name "Net-(U1-BST)") (class "Default")
      (node (ref "C1") (pin "2") (pinfunction "2_2") (pintype "passive"))
      (node (ref "U1") (pin "1") (pinfunction "BST_1") (pintype "passive"))
    )
    (net (code "141") (name "Net-(U1-EN)") (class "Default")
      (node (ref "R3") (pin "2") (pinfunction "2_2") (pintype "passive"))
      (node (ref "R4") (pin "1") (pinfunction "1_1") (pintype "passive"))
      (node (ref "U1") (pin "4") (pinfunction "EN_4") (pintype "passive"))
    )
    (net (code "142") (name "Net-(U1-FB)") (class "Default")
      (node (ref "C4") (pin "1") (pinfunction "1_1") (pintype "passive"))
      (node (ref "R2") (pin "1") (pinfunction "1_1") (pintype "passive"))
      (node (ref "R5") (pin "2") (pinfunction "2_2") (pintype "passive"))
      (node (ref "U1") (pin "3") (pinfunction "FB_3") (pintype "passive"))
    )
    (net (code "143") (name "Net-(U4-A)") (class "Default")
      (node (ref "R33") (pin "2") (pinfunction "2_2") (pintype "passive"))
      (node (ref "U4") (pin "1") (pinfunction "A_1") (pintype "passive"))
    )
    (net (code "144") (name "Net-(U5-A)") (class "Default")
      (node (ref "R34") (pin "2") (pinfunction "2_2") (pintype "passive"))
      (node (ref "U5") (pin "1") (pinfunction "A_1") (pintype "passive"))
    )
    (net (code "145") (name "Net-(U6-A)") (class "Default")
      (node (ref "R35") (pin "2") (pinfunction "2_2") (pintype "passive"))
      (node (ref "U6") (pin "1") (pinfunction "A_1") (pintype "passive"))
    )
    (net (code "146") (name "Net-(U7-A)") (class "Default")
      (node (ref "R36") (pin "2") (pinfunction "2_2") (pintype "passive"))
      (node (ref "U7") (pin "1") (pinfunction "A_1") (pintype "passive"))
    )
    (net (code "147") (name "Net-(U8-A)") (class "Default")
      (node (ref "R37") (pin "2") (pinfunction "2_2") (pintype "passive"))
      (node (ref "U8") (pin "1") (pinfunction "A_1") (pintype "passive"))
    )
    (net (code "148") (name "Net-(U9-A)") (class "Default")
      (node (ref "R38") (pin "2") (pinfunction "2_2") (pintype "passive"))
      (node (ref "U9") (pin "1") (pinfunction "A_1") (pintype "passive"))
    )
    (net (code "149") (name "Net-(U10-A)") (class "Default")
      (node (ref "R39") (pin "2") (pinfunction "2_2") (pintype "passive"))
      (node (ref "U10") (pin "1") (pinfunction "A_1") (pintype "passive"))
    )
    (net (code "150") (name "Net-(U11-A)") (class "Default")
      (node (ref "R40") (pin "2") (pinfunction "2_2") (pintype "passive"))
      (node (ref "U11") (pin "1") (pinfunction "A_1") (pintype "passive"))
    )
    (net (code "151") (name "Net-(U12-A)") (class "Default")
      (node (ref "R41") (pin "2") (pinfunction "2_2") (pintype "passive"))
      (node (ref "U12") (pin "1") (pinfunction "A_1") (pintype "passive"))
    )
    (net (code "152") (name "Net-(U13-A)") (class "Default")
      (node (ref "R42") (pin "2") (pinfunction "2_2") (pintype "passive"))
      (node (ref "U13") (pin "1") (pinfunction "A_1") (pintype "passive"))
    )
    (net (code "153") (name "Net-(U14-A)") (class "Default")
      (node (ref "R43") (pin "2") (pinfunction "2_2") (pintype "passive"))
      (node (ref "U14") (pin "1") (pinfunction "A_1") (pintype "passive"))
    )
    (net (code "154") (name "Net-(U15-A)") (class "Default")
      (node (ref "R44") (pin "2") (pinfunction "2_2") (pintype "passive"))
      (node (ref "U15") (pin "1") (pinfunction "A_1") (pintype "passive"))
    )
    (net (code "155") (name "Net-(U16-A)") (class "Default")
      (node (ref "R45") (pin "2") (pinfunction "2_2") (pintype "passive"))
      (node (ref "U16") (pin "1") (pinfunction "A_1") (pintype "passive"))
    )
    (net (code "156") (name "Net-(U17-A)") (class "Default")
      (node (ref "R46") (pin "2") (pinfunction "2_2") (pintype "passive"))
      (node (ref "U17") (pin "1") (pinfunction "A_1") (pintype "passive"))
    )
    (net (code "157") (name "Net-(U18-A)") (class "Default")
      (node (ref "R47") (pin "2") (pinfunction "2_2") (pintype "passive"))
      (node (ref "U18") (pin "1") (pinfunction "A_1") (pintype "passive"))
    )
    (net (code "158") (name "Net-(U19-A)") (class "Default")
      (node (ref "R48") (pin "2") (pinfunction "2_2") (pintype "passive"))
      (node (ref "U19") (pin "1") (pinfunction "A_1") (pintype "passive"))
    )
    (net (code "159") (name "Vin") (class "Default")
      (node (ref "D2") (pin "1") (pinfunction "A_1") (pintype "passive"))
      (node (ref "P1") (pin "2") (pinfunction "2_2") (pintype "passive"))
    )
    (net (code "160") (name "unconnected-(IC1-CBUS2-Pad14)") (class "Default")
      (node (ref "IC1") (pin "14") (pinfunction "CBUS2_14") (pintype "passive"))
    )
    (net (code "161") (name "unconnected-(IC1-CBUS3-Pad13)") (class "Default")
      (node (ref "IC1") (pin "13") (pinfunction "CBUS3_13") (pintype "passive"))
    )
    (net (code "162") (name "unconnected-(IC1-CBUS4-Pad12)") (class "Default")
      (node (ref "IC1") (pin "12") (pinfunction "CBUS4_12") (pintype "passive"))
    )
    (net (code "163") (name "unconnected-(IC1-CTS#-Pad11)") (class "Default")
      (node (ref "IC1") (pin "11") (pinfunction "CTS#_11") (pintype "passive"))
    )
    (net (code "164") (name "unconnected-(IC1-DCD#-Pad10)") (class "Default")
      (node (ref "IC1") (pin "10") (pinfunction "DCD#_10") (pintype "passive"))
    )
    (net (code "165") (name "unconnected-(IC1-DSR#-Pad9)") (class "Default")
      (node (ref "IC1") (pin "9") (pinfunction "DSR#_9") (pintype "passive"))
    )
    (net (code "166") (name "unconnected-(IC1-DTR#-Pad2)") (class "Default")
      (node (ref "IC1") (pin "2") (pinfunction "DTR#_2") (pintype "passive"))
    )
    (net (code "167") (name "unconnected-(IC1-NC-Pad8)") (class "Default")
      (node (ref "IC1") (pin "8") (pinfunction "NC_8") (pintype "passive"))
    )
    (net (code "168") (name "unconnected-(IC1-NC-Pad24)") (class "Default")
      (node (ref "IC1") (pin "24") (pinfunction "NC_24") (pintype "passive"))
    )
    (net (code "169") (name "unconnected-(IC1-OSCI-Pad27)") (class "Default")
      (node (ref "IC1") (pin "27") (pinfunction "OSCI_27") (pintype "passive"))
    )
    (net (code "170") (name "unconnected-(IC1-OSCO-Pad28)") (class "Default")
      (node (ref "IC1") (pin "28") (pinfunction "OSCO_28") (pintype "passive"))
    )
    (net (code "171") (name "unconnected-(IC1-RI#-Pad6)") (class "Default")
      (node (ref "IC1") (pin "6") (pinfunction "RI#_6") (pintype "passive"))
    )
    (net (code "172") (name "unconnected-(IC1-RTS#-Pad3)") (class "Default")
      (node (ref "IC1") (pin "3") (pinfunction "RTS#_3") (pintype "passive"))
    )
    (net (code "173") (name "unconnected-(U2-EX_LVD-Pad29)") (class "Default")
      (node (ref "U2") (pin "29") (pinfunction "EX_LVD_29") (pintype "passive"))
    )
    (net (code "174") (name "unconnected-(U2-NA-Pad26)") (class "Default")
      (node (ref "U2") (pin "26") (pinfunction "NA_26") (pintype "passive"))
    )
    (net (code "175") (name "unconnected-(U22-1A-Pad1)") (class "Default")
      (node (ref "U22") (pin "1") (pinfunction "1A_1") (pintype "passive"))
    )
    (net (code "176") (name "unconnected-(U22-1Y-Pad2)") (class "Default")
      (node (ref "U22") (pin "2") (pinfunction "1Y_2") (pintype "passive"))
    )
    (net (code "177") (name "unconnected-(U22-2A-Pad3)") (class "Default")
      (node (ref "U22") (pin "3") (pinfunction "2A_3") (pintype "passive"))
    )
    (net (code "178") (name "unconnected-(U22-2Y-Pad4)") (class "Default")
      (node (ref "U22") (pin "4") (pinfunction "2Y_4") (pintype "passive"))
    )
  )
)
